# Eddy_Backplane.net
KiCad netlist of a schematic drawn in EAGLE
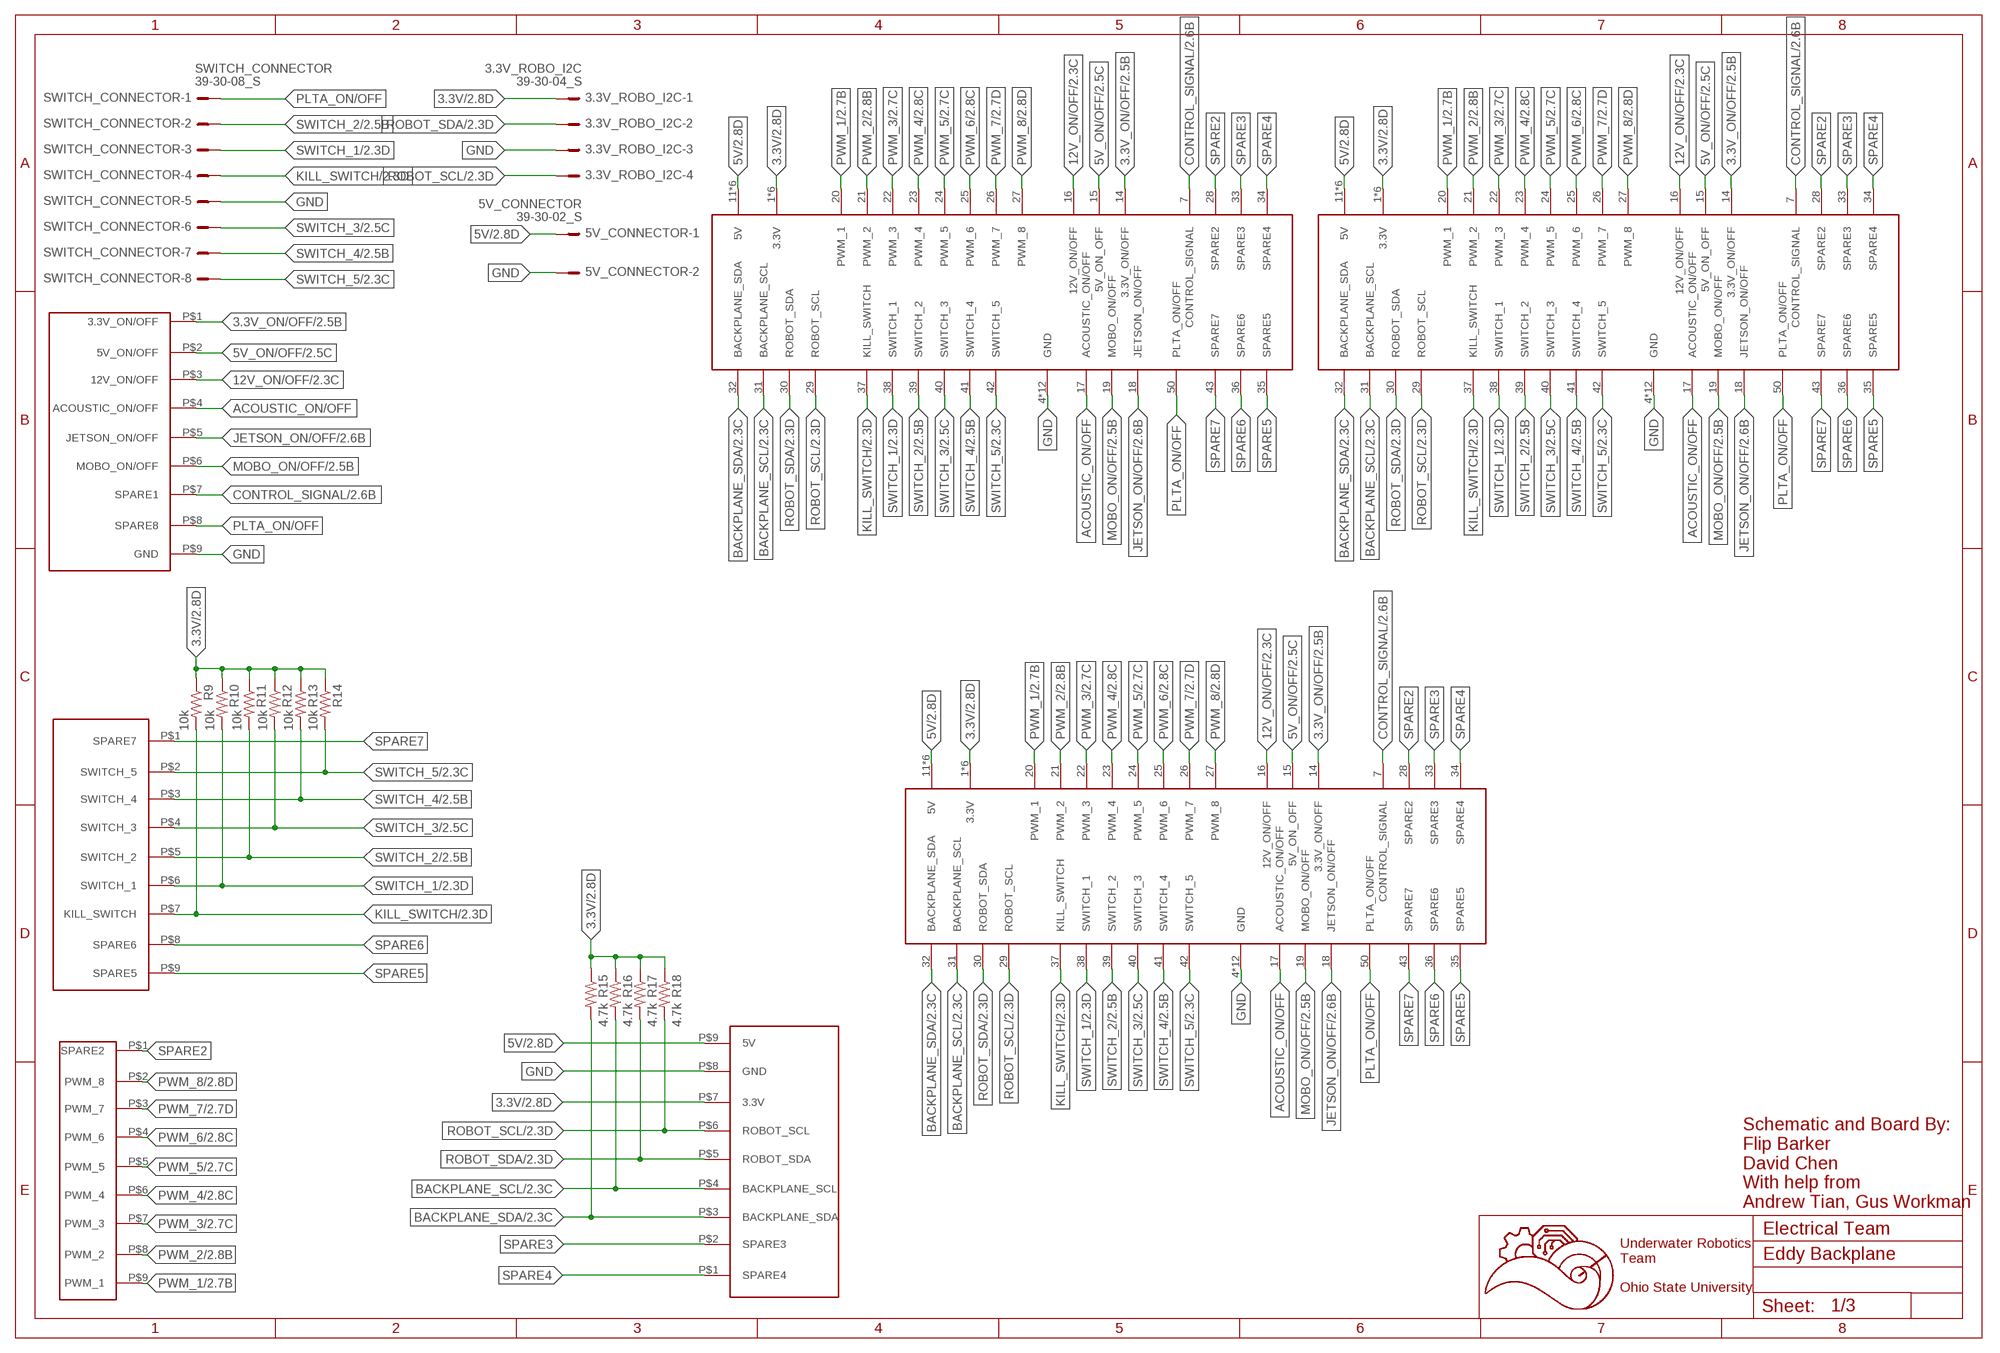
[diagram p0: schematic, sheet 1]
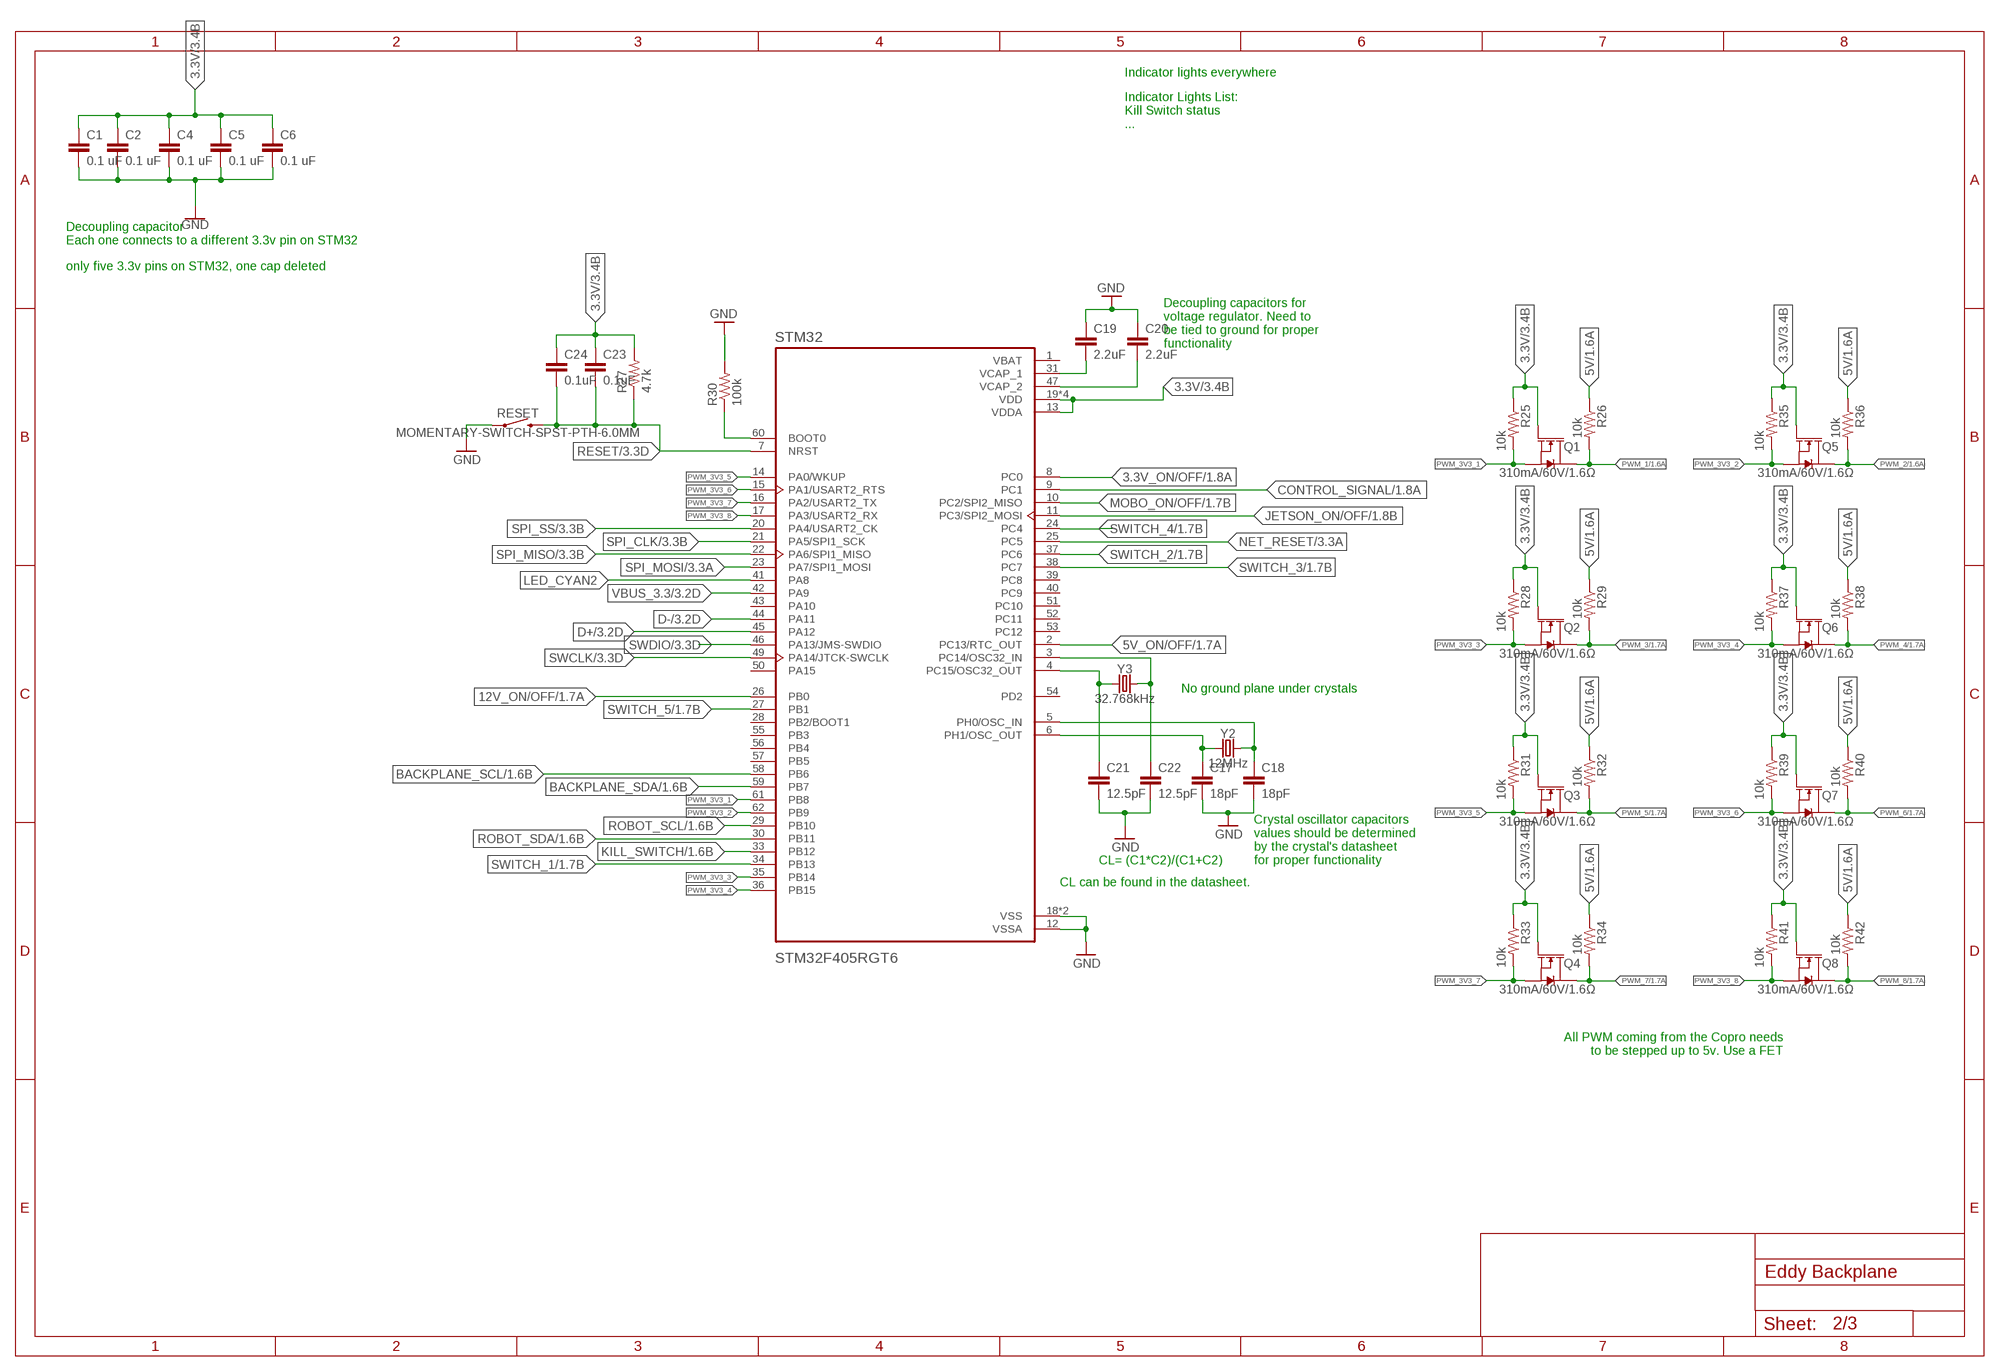
[diagram p1: schematic, sheet 2]
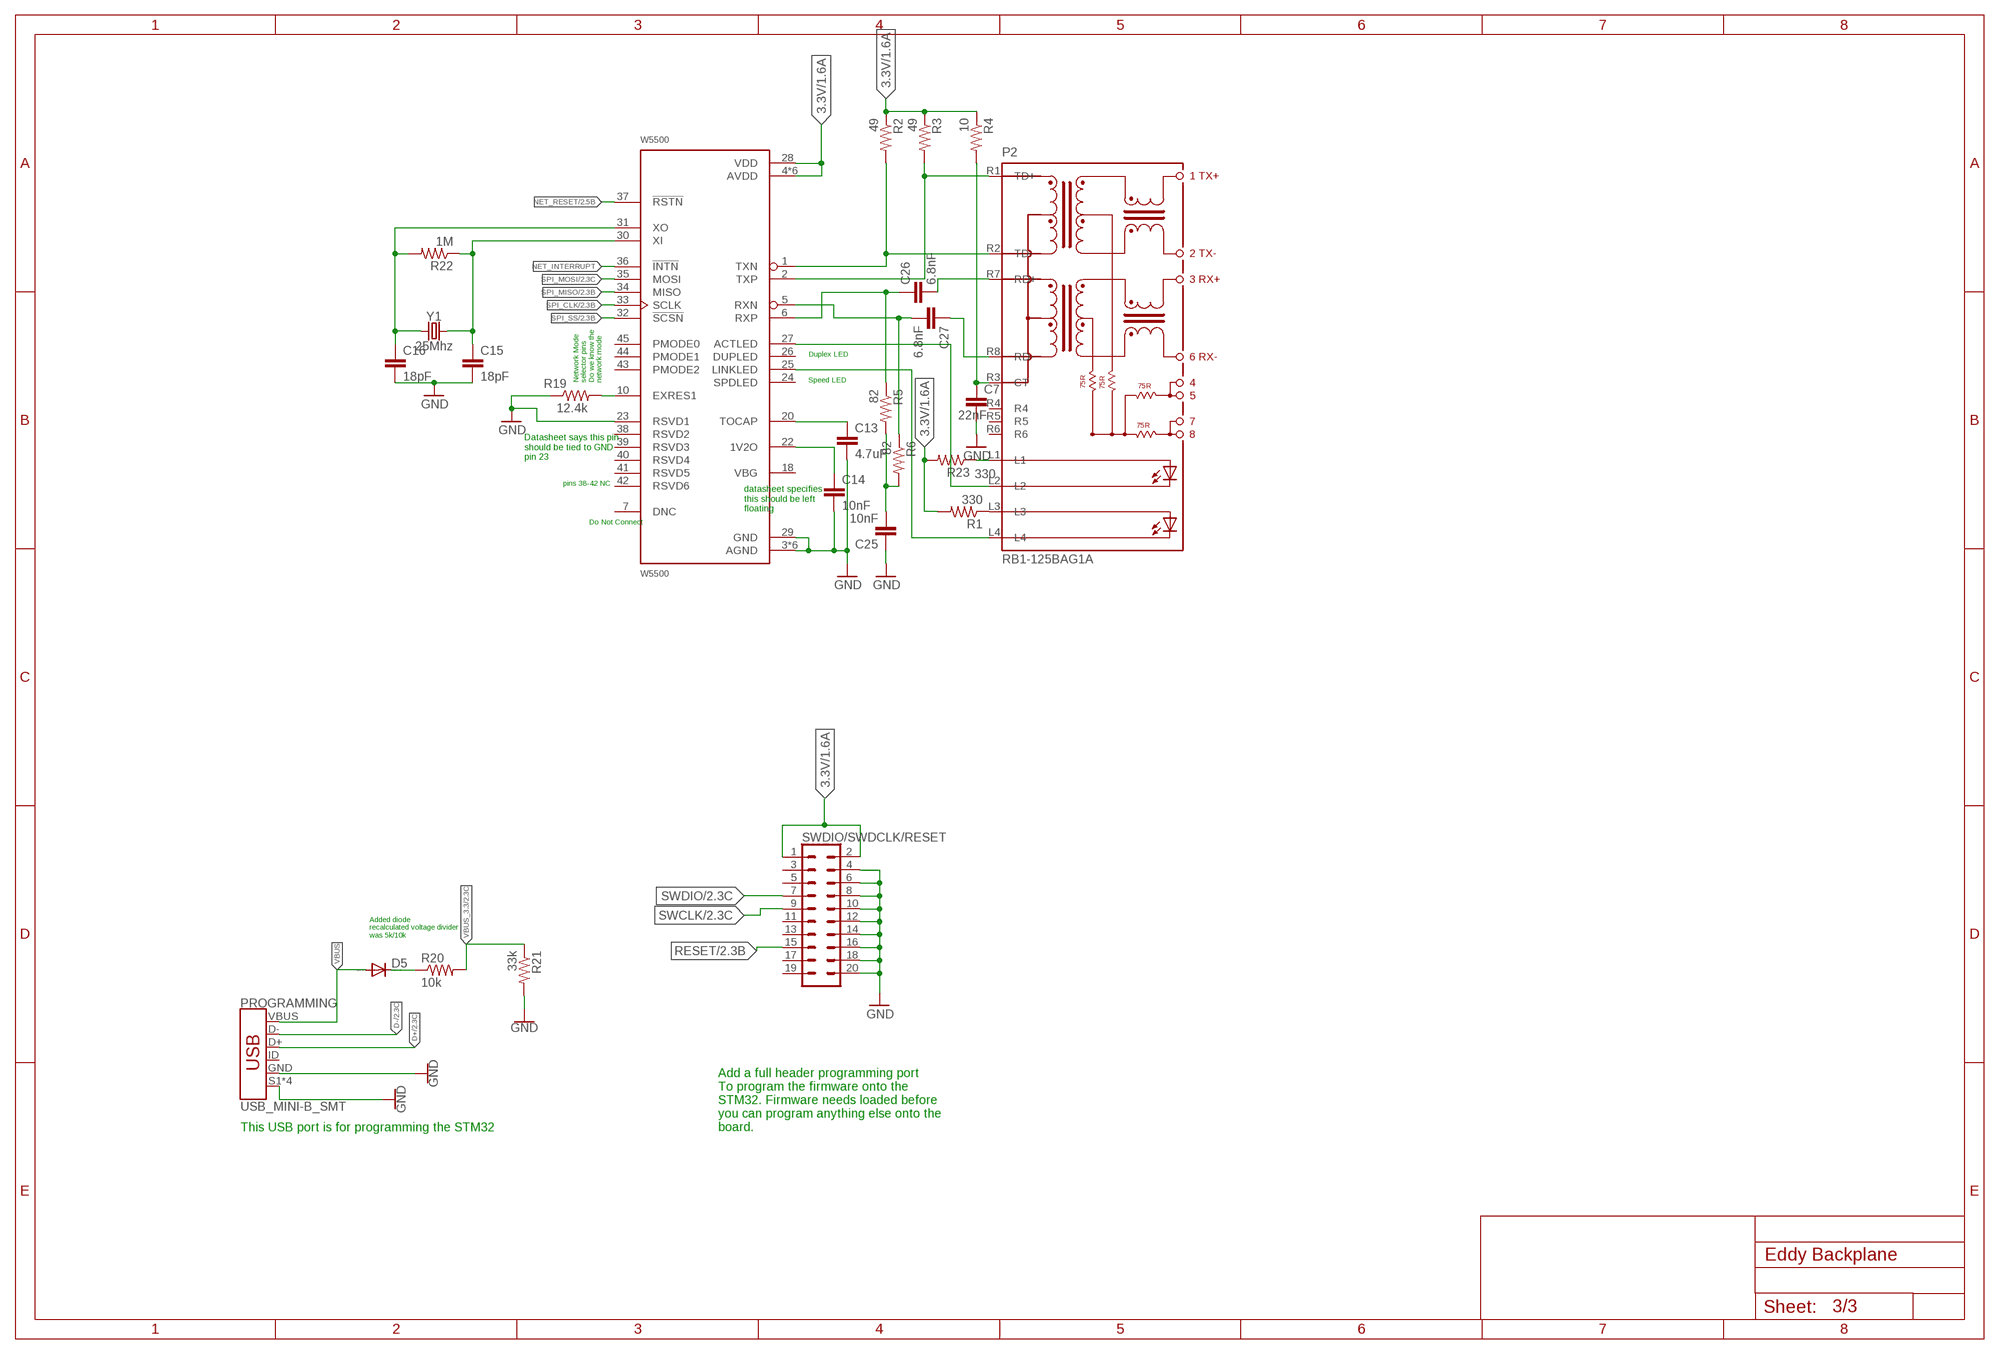
[diagram p2: schematic, sheet 3]

(export (version "E")
  (design (tool "Eeschema 10.0.6"))
  (components
    (comp (ref "C7")
      (value "22nF")
      (footprint "eagle-import:C0603")
      (libsource (lib "eagle-import") (part "C-EUC0603"))
    )
    (comp (ref "C13")
      (value "4.7uF")
      (footprint "eagle-import:C0603")
      (libsource (lib "eagle-import") (part "C-EUC0603"))
    )
    (comp (ref "C14")
      (value "10nF")
      (footprint "eagle-import:C0603")
      (libsource (lib "eagle-import") (part "C-EUC0603"))
    )
    (comp (ref "C15")
      (value "18pF")
      (footprint "eagle-import:C0603")
      (libsource (lib "eagle-import") (part "C-EUC0603"))
    )
    (comp (ref "C16")
      (value "18pF")
      (footprint "eagle-import:C0603")
      (libsource (lib "eagle-import") (part "C-EUC0603"))
    )
    (comp (ref "C25")
      (value "10nF")
      (footprint "eagle-import:C0603")
      (libsource (lib "eagle-import") (part "C-EUC0603"))
    )
    (comp (ref "C26")
      (value "6.8nF")
      (footprint "eagle-import:C0603")
      (libsource (lib "eagle-import") (part "C-EUC0603"))
    )
    (comp (ref "C27")
      (value "6.8nF")
      (footprint "eagle-import:C0603")
      (libsource (lib "eagle-import") (part "C-EUC0603"))
    )
    (comp (ref "D5")
      (value "DIODE-SMB")
      (footprint "eagle-import:SMB")
      (libsource (lib "eagle-import") (part "DIODE-SMB"))
    )
    (comp (ref "P2")
      (value "RB1-125BAG1A")
      (footprint "eagle-import:WIZNET_RB1-125BAG1A")
      (fields (field (name "MF") "WIZnet"))
      (libsource (lib "eagle-import") (part "RB1-125BAG1A"))
    )
    (comp (ref "PROGRAMMING")
      (value "USB_MINI-B_SMT")
      (footprint "eagle-import:USB-MINIB")
      (libsource (lib "eagle-import") (part "USB_MINI-B_SMT"))
    )
    (comp (ref "R1")
      (value "330")
      (footprint "eagle-import:R0603")
      (libsource (lib "eagle-import") (part "R-US_R0603"))
    )
    (comp (ref "R2")
      (value "49")
      (footprint "eagle-import:R0603")
      (libsource (lib "eagle-import") (part "R-US_R0603"))
    )
    (comp (ref "R3")
      (value "49")
      (footprint "eagle-import:R0603")
      (libsource (lib "eagle-import") (part "R-US_R0603"))
    )
    (comp (ref "R4")
      (value "10")
      (footprint "eagle-import:R0603")
      (libsource (lib "eagle-import") (part "R-US_R0603"))
    )
    (comp (ref "R5")
      (value "82")
      (footprint "eagle-import:R0603")
      (libsource (lib "eagle-import") (part "R-US_R0603"))
    )
    (comp (ref "R6")
      (value "82")
      (footprint "eagle-import:R0603")
      (libsource (lib "eagle-import") (part "R-US_R0603"))
    )
    (comp (ref "R19")
      (value "12.4k")
      (footprint "eagle-import:R0603")
      (libsource (lib "eagle-import") (part "R-US_R0603"))
    )
    (comp (ref "R20")
      (value "10k")
      (footprint "eagle-import:R0603")
      (libsource (lib "eagle-import") (part "R-US_R0603"))
    )
    (comp (ref "R21")
      (value "33k")
      (footprint "eagle-import:R0603")
      (libsource (lib "eagle-import") (part "R-US_R0603"))
    )
    (comp (ref "R22")
      (value "1M")
      (footprint "eagle-import:R0603")
      (libsource (lib "eagle-import") (part "R-US_R0603"))
    )
    (comp (ref "R23")
      (value "330")
      (footprint "eagle-import:R0603")
      (libsource (lib "eagle-import") (part "R-US_R0603"))
    )
    (comp (ref "SWDIO/SWDCLK/RESET")
      (value "CONN_10X2")
      (footprint "eagle-import:2X10")
      (libsource (lib "eagle-import") (part "CONN_10X2"))
    )
    (comp (ref "W5500")
      (value "W5500")
      (footprint "eagle-import:QFP50P900X900X160-48N")
      (fields (field (name "MF") "WIZnet"))
      (libsource (lib "eagle-import") (part "W5500"))
    )
    (comp (ref "Y1")
      (value "25Mhz")
      (footprint "eagle-import:HC49US")
      (libsource (lib "eagle-import") (part "CRYSTALPTH-HC49US"))
    )
    (comp (ref "3.3V_ROBO_I2C")
      (value "39-30-04_S")
      (footprint "eagle-import:39-30-_04_")
      (libsource (lib "eagle-import") (part "39-30-?04?_S"))
    )
    (comp (ref "5V_CONNECTOR")
      (value "39-30-02_S")
      (footprint "eagle-import:39-30-_02_")
      (libsource (lib "eagle-import") (part "39-30-?02?_S"))
    )
    (comp (ref "PWR_ON")
      (value "929870-01-09_3")
      (footprint "eagle-import:929852-01-09_1ROW")
      (libsource (lib "eagle-import") (part "929870-01-09_3"))
    )
    (comp (ref "R9")
      (value "10k")
      (footprint "eagle-import:R0603")
      (libsource (lib "eagle-import") (part "R-US_R0603"))
    )
    (comp (ref "R10")
      (value "10k")
      (footprint "eagle-import:R0603")
      (libsource (lib "eagle-import") (part "R-US_R0603"))
    )
    (comp (ref "R11")
      (value "10k")
      (footprint "eagle-import:R0603")
      (libsource (lib "eagle-import") (part "R-US_R0603"))
    )
    (comp (ref "R12")
      (value "10k")
      (footprint "eagle-import:R0603")
      (libsource (lib "eagle-import") (part "R-US_R0603"))
    )
    (comp (ref "R13")
      (value "10k")
      (footprint "eagle-import:R0603")
      (libsource (lib "eagle-import") (part "R-US_R0603"))
    )
    (comp (ref "R14")
      (value "10k")
      (footprint "eagle-import:R0603")
      (libsource (lib "eagle-import") (part "R-US_R0603"))
    )
    (comp (ref "R15")
      (value "4.7k")
      (footprint "eagle-import:R0603")
      (libsource (lib "eagle-import") (part "R-US_R0603"))
    )
    (comp (ref "R16")
      (value "4.7k")
      (footprint "eagle-import:R0603")
      (libsource (lib "eagle-import") (part "R-US_R0603"))
    )
    (comp (ref "R17")
      (value "4.7k")
      (footprint "eagle-import:R0603")
      (libsource (lib "eagle-import") (part "R-US_R0603"))
    )
    (comp (ref "R18")
      (value "4.7k")
      (footprint "eagle-import:R0603")
      (libsource (lib "eagle-import") (part "R-US_R0603"))
    )
    (comp (ref "SWITCH_CONN")
      (value "929870-01-09_1")
      (footprint "eagle-import:929852-01-09_1ROW")
      (libsource (lib "eagle-import") (part "929870-01-09_1"))
    )
    (comp (ref "SWITCH_CONNECTOR")
      (value "39-30-08_S")
      (footprint "eagle-import:39-30-_08_")
      (libsource (lib "eagle-import") (part "39-30-?08?_S"))
    )
    (comp (ref "U$1")
      (value "5530843-FEMALE")
      (footprint "eagle-import:5530843-6-BACKPLANEMATE")
      (libsource (lib "eagle-import") (part "5530843-FEMALE"))
    )
    (comp (ref "U$2")
      (value "5530843-FEMALE")
      (footprint "eagle-import:5530843-6-BACKPLANEMATE")
      (libsource (lib "eagle-import") (part "5530843-FEMALE"))
    )
    (comp (ref "U$3")
      (value "5530843-FEMALE")
      (footprint "eagle-import:5530843-6-BACKPLANEMATE")
      (libsource (lib "eagle-import") (part "5530843-FEMALE"))
    )
    (comp (ref "U$6")
      (value "929870-01-09_2")
      (footprint "eagle-import:929852-01-09_1ROW")
      (libsource (lib "eagle-import") (part "929870-01-09_2"))
    )
    (comp (ref "U$8")
      (value "929870-01-09_4")
      (footprint "eagle-import:929852-01-09_1ROW")
      (libsource (lib "eagle-import") (part "929870-01-09_4"))
    )
    (comp (ref "C1")
      (value "0.1 uF")
      (footprint "eagle-import:C0603")
      (libsource (lib "eagle-import") (part "C-EUC0603"))
    )
    (comp (ref "C2")
      (value "0.1 uF")
      (footprint "eagle-import:C0603")
      (libsource (lib "eagle-import") (part "C-EUC0603"))
    )
    (comp (ref "C4")
      (value "0.1 uF")
      (footprint "eagle-import:C0603")
      (libsource (lib "eagle-import") (part "C-EUC0603"))
    )
    (comp (ref "C5")
      (value "0.1 uF")
      (footprint "eagle-import:C0603")
      (libsource (lib "eagle-import") (part "C-EUC0603"))
    )
    (comp (ref "C6")
      (value "0.1 uF")
      (footprint "eagle-import:C0603")
      (libsource (lib "eagle-import") (part "C-EUC0603"))
    )
    (comp (ref "C17")
      (value "18pF")
      (footprint "eagle-import:C0603")
      (libsource (lib "eagle-import") (part "C-EUC0603"))
    )
    (comp (ref "C18")
      (value "18pF")
      (footprint "eagle-import:C0603")
      (libsource (lib "eagle-import") (part "C-EUC0603"))
    )
    (comp (ref "C19")
      (value "2.2uF")
      (footprint "eagle-import:C0603")
      (libsource (lib "eagle-import") (part "C-EUC0603"))
    )
    (comp (ref "C20")
      (value "2.2uF")
      (footprint "eagle-import:C0603")
      (libsource (lib "eagle-import") (part "C-EUC0603"))
    )
    (comp (ref "C21")
      (value "12.5pF")
      (footprint "eagle-import:C0603")
      (libsource (lib "eagle-import") (part "C-EUC0603"))
    )
    (comp (ref "C22")
      (value "12.5pF")
      (footprint "eagle-import:C0603")
      (libsource (lib "eagle-import") (part "C-EUC0603"))
    )
    (comp (ref "C23")
      (value "0.1uF")
      (footprint "eagle-import:C0603")
      (libsource (lib "eagle-import") (part "C-EUC0603"))
    )
    (comp (ref "C24")
      (value "0.1uF")
      (footprint "eagle-import:C0603")
      (libsource (lib "eagle-import") (part "C-EUC0603"))
    )
    (comp (ref "Q1")
      (value "310mA/60V/1.6Ω")
      (footprint "eagle-import:SOT323")
      (libsource (lib "eagle-import") (part "MOSFET-NCH-2N7002PW"))
    )
    (comp (ref "Q2")
      (value "310mA/60V/1.6Ω")
      (footprint "eagle-import:SOT323")
      (libsource (lib "eagle-import") (part "MOSFET-NCH-2N7002PW"))
    )
    (comp (ref "Q3")
      (value "310mA/60V/1.6Ω")
      (footprint "eagle-import:SOT323")
      (libsource (lib "eagle-import") (part "MOSFET-NCH-2N7002PW"))
    )
    (comp (ref "Q4")
      (value "310mA/60V/1.6Ω")
      (footprint "eagle-import:SOT323")
      (libsource (lib "eagle-import") (part "MOSFET-NCH-2N7002PW"))
    )
    (comp (ref "Q5")
      (value "310mA/60V/1.6Ω")
      (footprint "eagle-import:SOT323")
      (libsource (lib "eagle-import") (part "MOSFET-NCH-2N7002PW"))
    )
    (comp (ref "Q6")
      (value "310mA/60V/1.6Ω")
      (footprint "eagle-import:SOT323")
      (libsource (lib "eagle-import") (part "MOSFET-NCH-2N7002PW"))
    )
    (comp (ref "Q7")
      (value "310mA/60V/1.6Ω")
      (footprint "eagle-import:SOT323")
      (libsource (lib "eagle-import") (part "MOSFET-NCH-2N7002PW"))
    )
    (comp (ref "Q8")
      (value "310mA/60V/1.6Ω")
      (footprint "eagle-import:SOT323")
      (libsource (lib "eagle-import") (part "MOSFET-NCH-2N7002PW"))
    )
    (comp (ref "R25")
      (value "10k")
      (footprint "eagle-import:R0603")
      (libsource (lib "eagle-import") (part "R-US_R0603"))
    )
    (comp (ref "R26")
      (value "10k")
      (footprint "eagle-import:R0603")
      (libsource (lib "eagle-import") (part "R-US_R0603"))
    )
    (comp (ref "R27")
      (value "4.7k")
      (footprint "eagle-import:R0603")
      (libsource (lib "eagle-import") (part "R-US_R0603"))
    )
    (comp (ref "R28")
      (value "10k")
      (footprint "eagle-import:R0603")
      (libsource (lib "eagle-import") (part "R-US_R0603"))
    )
    (comp (ref "R29")
      (value "10k")
      (footprint "eagle-import:R0603")
      (libsource (lib "eagle-import") (part "R-US_R0603"))
    )
    (comp (ref "R30")
      (value "100k")
      (footprint "eagle-import:R0603")
      (libsource (lib "eagle-import") (part "R-US_R0603"))
    )
    (comp (ref "R31")
      (value "10k")
      (footprint "eagle-import:R0603")
      (libsource (lib "eagle-import") (part "R-US_R0603"))
    )
    (comp (ref "R32")
      (value "10k")
      (footprint "eagle-import:R0603")
      (libsource (lib "eagle-import") (part "R-US_R0603"))
    )
    (comp (ref "R33")
      (value "10k")
      (footprint "eagle-import:R0603")
      (libsource (lib "eagle-import") (part "R-US_R0603"))
    )
    (comp (ref "R34")
      (value "10k")
      (footprint "eagle-import:R0603")
      (libsource (lib "eagle-import") (part "R-US_R0603"))
    )
    (comp (ref "R35")
      (value "10k")
      (footprint "eagle-import:R0603")
      (libsource (lib "eagle-import") (part "R-US_R0603"))
    )
    (comp (ref "R36")
      (value "10k")
      (footprint "eagle-import:R0603")
      (libsource (lib "eagle-import") (part "R-US_R0603"))
    )
    (comp (ref "R37")
      (value "10k")
      (footprint "eagle-import:R0603")
      (libsource (lib "eagle-import") (part "R-US_R0603"))
    )
    (comp (ref "R38")
      (value "10k")
      (footprint "eagle-import:R0603")
      (libsource (lib "eagle-import") (part "R-US_R0603"))
    )
    (comp (ref "R39")
      (value "10k")
      (footprint "eagle-import:R0603")
      (libsource (lib "eagle-import") (part "R-US_R0603"))
    )
    (comp (ref "R40")
      (value "10k")
      (footprint "eagle-import:R0603")
      (libsource (lib "eagle-import") (part "R-US_R0603"))
    )
    (comp (ref "R41")
      (value "10k")
      (footprint "eagle-import:R0603")
      (libsource (lib "eagle-import") (part "R-US_R0603"))
    )
    (comp (ref "R42")
      (value "10k")
      (footprint "eagle-import:R0603")
      (libsource (lib "eagle-import") (part "R-US_R0603"))
    )
    (comp (ref "RESET")
      (value "MOMENTARY-SWITCH-SPST-PTH-6.0MM")
      (footprint "eagle-import:TACTILE_SWITCH_PTH_6.0MM")
      (libsource (lib "eagle-import") (part "MOMENTARY-SWITCH-SPST-PTH-6.0MM"))
    )
    (comp (ref "STM32")
      (value "STM32F405RGT6")
      (footprint "eagle-import:QFP50P1200X1200X160-64N")
      (fields (field (name "MF") "STMicroelectronics"))
      (libsource (lib "eagle-import") (part "STM32F405RGT6"))
    )
    (comp (ref "Y2")
      (value "12MHz")
      (footprint "eagle-import:HC49US")
      (libsource (lib "eagle-import") (part "CRYSTAL-16MHZPTH-HC49US"))
    )
    (comp (ref "Y3")
      (value "32.768kHz")
      (footprint "eagle-import:CRYSTAL-SMD-3.2X1.5MM")
      (libsource (lib "eagle-import") (part "CRYSTAL-32.768KHZSMD-3.2X1.5"))
    )
  )
  (nets
    (net (code "1") (name "3.3V") (class "Default")
      (node (ref "3.3V_ROBO_I2C") (pin "1") (pinfunction "P_1") (pintype "passive"))
      (node (ref "C1") (pin "1") (pinfunction "1_1") (pintype "passive"))
      (node (ref "C2") (pin "1") (pinfunction "1_1") (pintype "passive"))
      (node (ref "C23") (pin "1") (pinfunction "1_1") (pintype "passive"))
      (node (ref "C24") (pin "1") (pinfunction "1_1") (pintype "passive"))
      (node (ref "C4") (pin "1") (pinfunction "1_1") (pintype "passive"))
      (node (ref "C5") (pin "1") (pinfunction "1_1") (pintype "passive"))
      (node (ref "C6") (pin "1") (pinfunction "1_1") (pintype "passive"))
      (node (ref "Q1") (pin "1") (pinfunction "G_1") (pintype "bidirectional"))
      (node (ref "Q2") (pin "1") (pinfunction "G_1") (pintype "bidirectional"))
      (node (ref "Q3") (pin "1") (pinfunction "G_1") (pintype "bidirectional"))
      (node (ref "Q4") (pin "1") (pinfunction "G_1") (pintype "bidirectional"))
      (node (ref "Q5") (pin "1") (pinfunction "G_1") (pintype "bidirectional"))
      (node (ref "Q6") (pin "1") (pinfunction "G_1") (pintype "bidirectional"))
      (node (ref "Q7") (pin "1") (pinfunction "G_1") (pintype "bidirectional"))
      (node (ref "Q8") (pin "1") (pinfunction "G_1") (pintype "bidirectional"))
      (node (ref "R1") (pin "2") (pinfunction "2_2") (pintype "passive"))
      (node (ref "R10") (pin "1") (pinfunction "1_1") (pintype "passive"))
      (node (ref "R11") (pin "1") (pinfunction "1_1") (pintype "passive"))
      (node (ref "R12") (pin "1") (pinfunction "1_1") (pintype "passive"))
      (node (ref "R13") (pin "1") (pinfunction "1_1") (pintype "passive"))
      (node (ref "R14") (pin "1") (pinfunction "1_1") (pintype "passive"))
      (node (ref "R15") (pin "1") (pinfunction "1_1") (pintype "passive"))
      (node (ref "R16") (pin "1") (pinfunction "1_1") (pintype "passive"))
      (node (ref "R17") (pin "1") (pinfunction "1_1") (pintype "passive"))
      (node (ref "R18") (pin "1") (pinfunction "1_1") (pintype "passive"))
      (node (ref "R2") (pin "1") (pinfunction "1_1") (pintype "passive"))
      (node (ref "R23") (pin "2") (pinfunction "2_2") (pintype "passive"))
      (node (ref "R25") (pin "1") (pinfunction "1_1") (pintype "passive"))
      (node (ref "R27") (pin "2") (pinfunction "2_2") (pintype "passive"))
      (node (ref "R28") (pin "1") (pinfunction "1_1") (pintype "passive"))
      (node (ref "R3") (pin "1") (pinfunction "1_1") (pintype "passive"))
      (node (ref "R31") (pin "1") (pinfunction "1_1") (pintype "passive"))
      (node (ref "R33") (pin "1") (pinfunction "1_1") (pintype "passive"))
      (node (ref "R35") (pin "1") (pinfunction "1_1") (pintype "passive"))
      (node (ref "R37") (pin "1") (pinfunction "1_1") (pintype "passive"))
      (node (ref "R39") (pin "1") (pinfunction "1_1") (pintype "passive"))
      (node (ref "R4") (pin "1") (pinfunction "1_1") (pintype "passive"))
      (node (ref "R41") (pin "1") (pinfunction "1_1") (pintype "passive"))
      (node (ref "R9") (pin "1") (pinfunction "1_1") (pintype "passive"))
      (node (ref "STM32") (pin "13") (pinfunction "VDDA_13") (pintype "power_in"))
      (node (ref "STM32") (pin "19") (pinfunction "VDD_19") (pintype "power_in"))
      (node (ref "STM32") (pin "32") (pinfunction "VDD_32") (pintype "power_in"))
      (node (ref "STM32") (pin "48") (pinfunction "VDD_48") (pintype "power_in"))
      (node (ref "STM32") (pin "64") (pinfunction "VDD_64") (pintype "power_in"))
      (node (ref "SWDIO/SWDCLK/RESET") (pin "1") (pinfunction "1_1") (pintype "passive"))
      (node (ref "SWDIO/SWDCLK/RESET") (pin "2") (pinfunction "2_2") (pintype "passive"))
      (node (ref "U$1") (pin "1") (pinfunction "3.3V_1") (pintype "bidirectional"))
      (node (ref "U$1") (pin "2") (pinfunction "3.3V_2") (pintype "bidirectional"))
      (node (ref "U$1") (pin "3") (pinfunction "3.3V_3") (pintype "bidirectional"))
      (node (ref "U$1") (pin "54") (pinfunction "3.3V_54") (pintype "bidirectional"))
      (node (ref "U$1") (pin "55") (pinfunction "3.3V_55") (pintype "bidirectional"))
      (node (ref "U$1") (pin "56") (pinfunction "3.3V_56") (pintype "bidirectional"))
      (node (ref "U$2") (pin "1") (pinfunction "3.3V_1") (pintype "bidirectional"))
      (node (ref "U$2") (pin "2") (pinfunction "3.3V_2") (pintype "bidirectional"))
      (node (ref "U$2") (pin "3") (pinfunction "3.3V_3") (pintype "bidirectional"))
      (node (ref "U$2") (pin "54") (pinfunction "3.3V_54") (pintype "bidirectional"))
      (node (ref "U$2") (pin "55") (pinfunction "3.3V_55") (pintype "bidirectional"))
      (node (ref "U$2") (pin "56") (pinfunction "3.3V_56") (pintype "bidirectional"))
      (node (ref "U$3") (pin "1") (pinfunction "3.3V_1") (pintype "bidirectional"))
      (node (ref "U$3") (pin "2") (pinfunction "3.3V_2") (pintype "bidirectional"))
      (node (ref "U$3") (pin "3") (pinfunction "3.3V_3") (pintype "bidirectional"))
      (node (ref "U$3") (pin "54") (pinfunction "3.3V_54") (pintype "bidirectional"))
      (node (ref "U$3") (pin "55") (pinfunction "3.3V_55") (pintype "bidirectional"))
      (node (ref "U$3") (pin "56") (pinfunction "3.3V_56") (pintype "bidirectional"))
      (node (ref "U$8") (pin "P$7") (pinfunction "3.3V_P$7") (pintype "bidirectional"))
      (node (ref "W5500") (pin "11") (pinfunction "AVDD_11") (pintype "power_in"))
      (node (ref "W5500") (pin "15") (pinfunction "AVDD_15") (pintype "power_in"))
      (node (ref "W5500") (pin "17") (pinfunction "AVDD_17") (pintype "power_in"))
      (node (ref "W5500") (pin "21") (pinfunction "AVDD_21") (pintype "power_in"))
      (node (ref "W5500") (pin "28") (pinfunction "VDD_28") (pintype "power_in"))
      (node (ref "W5500") (pin "4") (pinfunction "AVDD_4") (pintype "power_in"))
      (node (ref "W5500") (pin "8") (pinfunction "AVDD_8") (pintype "power_in"))
    )
    (net (code "2") (name "3.3V_ON{slash}OFF") (class "Default")
      (node (ref "PWR_ON") (pin "P$1") (pinfunction "3.3V_ON/OFF_P$1") (pintype "bidirectional"))
      (node (ref "STM32") (pin "8") (pinfunction "PC0_8") (pintype "bidirectional"))
      (node (ref "U$1") (pin "14") (pinfunction "3.3V_ON/OFF_14") (pintype "bidirectional"))
      (node (ref "U$2") (pin "14") (pinfunction "3.3V_ON/OFF_14") (pintype "bidirectional"))
      (node (ref "U$3") (pin "14") (pinfunction "3.3V_ON/OFF_14") (pintype "bidirectional"))
    )
    (net (code "3") (name "5V") (class "Default")
      (node (ref "5V_CONNECTOR") (pin "1") (pinfunction "P_1") (pintype "passive"))
      (node (ref "R26") (pin "1") (pinfunction "1_1") (pintype "passive"))
      (node (ref "R29") (pin "1") (pinfunction "1_1") (pintype "passive"))
      (node (ref "R32") (pin "1") (pinfunction "1_1") (pintype "passive"))
      (node (ref "R34") (pin "1") (pinfunction "1_1") (pintype "passive"))
      (node (ref "R36") (pin "1") (pinfunction "1_1") (pintype "passive"))
      (node (ref "R38") (pin "1") (pinfunction "1_1") (pintype "passive"))
      (node (ref "R40") (pin "1") (pinfunction "1_1") (pintype "passive"))
      (node (ref "R42") (pin "1") (pinfunction "1_1") (pintype "passive"))
      (node (ref "U$1") (pin "11") (pinfunction "5V_11") (pintype "bidirectional"))
      (node (ref "U$1") (pin "12") (pinfunction "5V_12") (pintype "bidirectional"))
      (node (ref "U$1") (pin "13") (pinfunction "5V_13") (pintype "bidirectional"))
      (node (ref "U$1") (pin "44") (pinfunction "5V_44") (pintype "bidirectional"))
      (node (ref "U$1") (pin "45") (pinfunction "5V_45") (pintype "bidirectional"))
      (node (ref "U$1") (pin "46") (pinfunction "5V_46") (pintype "bidirectional"))
      (node (ref "U$2") (pin "11") (pinfunction "5V_11") (pintype "bidirectional"))
      (node (ref "U$2") (pin "12") (pinfunction "5V_12") (pintype "bidirectional"))
      (node (ref "U$2") (pin "13") (pinfunction "5V_13") (pintype "bidirectional"))
      (node (ref "U$2") (pin "44") (pinfunction "5V_44") (pintype "bidirectional"))
      (node (ref "U$2") (pin "45") (pinfunction "5V_45") (pintype "bidirectional"))
      (node (ref "U$2") (pin "46") (pinfunction "5V_46") (pintype "bidirectional"))
      (node (ref "U$3") (pin "11") (pinfunction "5V_11") (pintype "bidirectional"))
      (node (ref "U$3") (pin "12") (pinfunction "5V_12") (pintype "bidirectional"))
      (node (ref "U$3") (pin "13") (pinfunction "5V_13") (pintype "bidirectional"))
      (node (ref "U$3") (pin "44") (pinfunction "5V_44") (pintype "bidirectional"))
      (node (ref "U$3") (pin "45") (pinfunction "5V_45") (pintype "bidirectional"))
      (node (ref "U$3") (pin "46") (pinfunction "5V_46") (pintype "bidirectional"))
      (node (ref "U$8") (pin "P$9") (pinfunction "5V_P$9") (pintype "bidirectional"))
    )
    (net (code "4") (name "5V_ON{slash}OFF") (class "Default")
      (node (ref "PWR_ON") (pin "P$2") (pinfunction "5V_ON/OFF_P$2") (pintype "bidirectional"))
      (node (ref "STM32") (pin "2") (pinfunction "PC13/RTC_OUT_2") (pintype "bidirectional"))
      (node (ref "U$1") (pin "15") (pinfunction "5V_ON_OFF_15") (pintype "bidirectional"))
      (node (ref "U$2") (pin "15") (pinfunction "5V_ON_OFF_15") (pintype "bidirectional"))
      (node (ref "U$3") (pin "15") (pinfunction "5V_ON_OFF_15") (pintype "bidirectional"))
    )
    (net (code "5") (name "12V_ON{slash}OFF") (class "Default")
      (node (ref "PWR_ON") (pin "P$3") (pinfunction "12V_ON/OFF_P$3") (pintype "bidirectional"))
      (node (ref "STM32") (pin "26") (pinfunction "PB0_26") (pintype "bidirectional"))
      (node (ref "U$1") (pin "16") (pinfunction "12V_ON/OFF_16") (pintype "bidirectional"))
      (node (ref "U$2") (pin "16") (pinfunction "12V_ON/OFF_16") (pintype "bidirectional"))
      (node (ref "U$3") (pin "16") (pinfunction "12V_ON/OFF_16") (pintype "bidirectional"))
    )
    (net (code "6") (name "ACOUSTIC_ON{slash}OFF") (class "Default")
      (node (ref "PWR_ON") (pin "P$4") (pinfunction "ACOUSTIC_ON/OFF_P$4") (pintype "bidirectional"))
      (node (ref "U$1") (pin "17") (pinfunction "ACOUSTIC_ON/OFF_17") (pintype "bidirectional"))
      (node (ref "U$2") (pin "17") (pinfunction "ACOUSTIC_ON/OFF_17") (pintype "bidirectional"))
      (node (ref "U$3") (pin "17") (pinfunction "ACOUSTIC_ON/OFF_17") (pintype "bidirectional"))
    )
    (net (code "7") (name "BACKPLANE_SCL") (class "Default")
      (node (ref "R16") (pin "2") (pinfunction "2_2") (pintype "passive"))
      (node (ref "STM32") (pin "58") (pinfunction "PB6_58") (pintype "bidirectional"))
      (node (ref "U$1") (pin "31") (pinfunction "BACKPLANE_SCL_31") (pintype "bidirectional"))
      (node (ref "U$2") (pin "31") (pinfunction "BACKPLANE_SCL_31") (pintype "bidirectional"))
      (node (ref "U$3") (pin "31") (pinfunction "BACKPLANE_SCL_31") (pintype "bidirectional"))
      (node (ref "U$8") (pin "P$4") (pinfunction "BACKPLANE_SCL_P$4") (pintype "bidirectional"))
    )
    (net (code "8") (name "BACKPLANE_SDA") (class "Default")
      (node (ref "R15") (pin "2") (pinfunction "2_2") (pintype "passive"))
      (node (ref "STM32") (pin "59") (pinfunction "PB7_59") (pintype "bidirectional"))
      (node (ref "U$1") (pin "32") (pinfunction "BACKPLANE_SDA_32") (pintype "bidirectional"))
      (node (ref "U$2") (pin "32") (pinfunction "BACKPLANE_SDA_32") (pintype "bidirectional"))
      (node (ref "U$3") (pin "32") (pinfunction "BACKPLANE_SDA_32") (pintype "bidirectional"))
      (node (ref "U$8") (pin "P$3") (pinfunction "BACKPLANE_SDA_P$3") (pintype "bidirectional"))
    )
    (net (code "9") (name "CONTROL_SIGNAL") (class "Default")
      (node (ref "PWR_ON") (pin "P$7") (pinfunction "SPARE1_P$7") (pintype "bidirectional"))
      (node (ref "STM32") (pin "9") (pinfunction "PC1_9") (pintype "bidirectional"))
      (node (ref "U$1") (pin "7") (pinfunction "CONTROL_SIGNAL_7") (pintype "bidirectional"))
      (node (ref "U$2") (pin "7") (pinfunction "CONTROL_SIGNAL_7") (pintype "bidirectional"))
      (node (ref "U$3") (pin "7") (pinfunction "CONTROL_SIGNAL_7") (pintype "bidirectional"))
    )
    (net (code "10") (name "D+") (class "Default")
      (node (ref "PROGRAMMING") (pin "D+") (pinfunction "D+_D+") (pintype "bidirectional"))
      (node (ref "STM32") (pin "45") (pinfunction "PA12_45") (pintype "bidirectional"))
    )
    (net (code "11") (name "D-") (class "Default")
      (node (ref "PROGRAMMING") (pin "D-") (pinfunction "D-_D-") (pintype "bidirectional"))
      (node (ref "STM32") (pin "44") (pinfunction "PA11_44") (pintype "bidirectional"))
    )
    (net (code "12") (name "GND") (class "Default")
      (node (ref "3.3V_ROBO_I2C") (pin "3") (pinfunction "P_3") (pintype "passive"))
      (node (ref "5V_CONNECTOR") (pin "2") (pinfunction "P_2") (pintype "passive"))
      (node (ref "C1") (pin "2") (pinfunction "2_2") (pintype "passive"))
      (node (ref "C13") (pin "2") (pinfunction "2_2") (pintype "passive"))
      (node (ref "C14") (pin "2") (pinfunction "2_2") (pintype "passive"))
      (node (ref "C15") (pin "2") (pinfunction "2_2") (pintype "passive"))
      (node (ref "C16") (pin "2") (pinfunction "2_2") (pintype "passive"))
      (node (ref "C17") (pin "2") (pinfunction "2_2") (pintype "passive"))
      (node (ref "C18") (pin "2") (pinfunction "2_2") (pintype "passive"))
      (node (ref "C19") (pin "1") (pinfunction "1_1") (pintype "passive"))
      (node (ref "C2") (pin "2") (pinfunction "2_2") (pintype "passive"))
      (node (ref "C20") (pin "1") (pinfunction "1_1") (pintype "passive"))
      (node (ref "C21") (pin "2") (pinfunction "2_2") (pintype "passive"))
      (node (ref "C22") (pin "2") (pinfunction "2_2") (pintype "passive"))
      (node (ref "C25") (pin "1") (pinfunction "1_1") (pintype "passive"))
      (node (ref "C4") (pin "2") (pinfunction "2_2") (pintype "passive"))
      (node (ref "C5") (pin "2") (pinfunction "2_2") (pintype "passive"))
      (node (ref "C6") (pin "2") (pinfunction "2_2") (pintype "passive"))
      (node (ref "C7") (pin "2") (pinfunction "2_2") (pintype "passive"))
      (node (ref "PROGRAMMING") (pin "GND") (pinfunction "GND_GND") (pintype "power_in"))
      (node (ref "PROGRAMMING") (pin "S1") (pinfunction "SHIELD_S1") (pintype "bidirectional"))
      (node (ref "PROGRAMMING") (pin "S2") (pinfunction "SHIELD_S2") (pintype "bidirectional"))
      (node (ref "PROGRAMMING") (pin "S3") (pinfunction "SHIELD_S3") (pintype "bidirectional"))
      (node (ref "PROGRAMMING") (pin "S4") (pinfunction "SHIELD_S4") (pintype "bidirectional"))
      (node (ref "PWR_ON") (pin "P$9") (pinfunction "GND_P$9") (pintype "bidirectional"))
      (node (ref "R19") (pin "1") (pinfunction "1_1") (pintype "passive"))
      (node (ref "R21") (pin "2") (pinfunction "2_2") (pintype "passive"))
      (node (ref "R30") (pin "2") (pinfunction "2_2") (pintype "passive"))
      (node (ref "RESET") (pin "1") (pinfunction "1_1") (pintype "passive"))
      (node (ref "STM32") (pin "12") (pinfunction "VSSA_12") (pintype "power_in"))
      (node (ref "STM32") (pin "18") (pinfunction "VSS_18") (pintype "power_in"))
      (node (ref "STM32") (pin "63") (pinfunction "VSS_63") (pintype "power_in"))
      (node (ref "SWDIO/SWDCLK/RESET") (pin "10") (pinfunction "10_10") (pintype "passive"))
      (node (ref "SWDIO/SWDCLK/RESET") (pin "12") (pinfunction "12_12") (pintype "passive"))
      (node (ref "SWDIO/SWDCLK/RESET") (pin "14") (pinfunction "14_14") (pintype "passive"))
      (node (ref "SWDIO/SWDCLK/RESET") (pin "16") (pinfunction "16_16") (pintype "passive"))
      (node (ref "SWDIO/SWDCLK/RESET") (pin "18") (pinfunction "18_18") (pintype "passive"))
      (node (ref "SWDIO/SWDCLK/RESET") (pin "20") (pinfunction "20_20") (pintype "passive"))
      (node (ref "SWDIO/SWDCLK/RESET") (pin "4") (pinfunction "4_4") (pintype "passive"))
      (node (ref "SWDIO/SWDCLK/RESET") (pin "6") (pinfunction "6_6") (pintype "passive"))
      (node (ref "SWDIO/SWDCLK/RESET") (pin "8") (pinfunction "8_8") (pintype "passive"))
      (node (ref "SWITCH_CONNECTOR") (pin "5") (pinfunction "P_5") (pintype "passive"))
      (node (ref "U$1") (pin "10") (pinfunction "GND_10") (pintype "bidirectional"))
      (node (ref "U$1") (pin "4") (pinfunction "GND_4") (pintype "bidirectional"))
      (node (ref "U$1") (pin "47") (pinfunction "GND_47") (pintype "bidirectional"))
      (node (ref "U$1") (pin "48") (pinfunction "GND_48") (pintype "bidirectional"))
      (node (ref "U$1") (pin "49") (pinfunction "GND_49") (pintype "bidirectional"))
      (node (ref "U$1") (pin "5") (pinfunction "GND_5") (pintype "bidirectional"))
      (node (ref "U$1") (pin "51") (pinfunction "GND_51") (pintype "bidirectional"))
      (node (ref "U$1") (pin "52") (pinfunction "GND_52") (pintype "bidirectional"))
      (node (ref "U$1") (pin "53") (pinfunction "GND_53") (pintype "bidirectional"))
      (node (ref "U$1") (pin "6") (pinfunction "GND_6") (pintype "bidirectional"))
      (node (ref "U$1") (pin "8") (pinfunction "GND_8") (pintype "bidirectional"))
      (node (ref "U$1") (pin "9") (pinfunction "GND_9") (pintype "bidirectional"))
      (node (ref "U$2") (pin "10") (pinfunction "GND_10") (pintype "bidirectional"))
      (node (ref "U$2") (pin "4") (pinfunction "GND_4") (pintype "bidirectional"))
      (node (ref "U$2") (pin "47") (pinfunction "GND_47") (pintype "bidirectional"))
      (node (ref "U$2") (pin "48") (pinfunction "GND_48") (pintype "bidirectional"))
      (node (ref "U$2") (pin "49") (pinfunction "GND_49") (pintype "bidirectional"))
      (node (ref "U$2") (pin "5") (pinfunction "GND_5") (pintype "bidirectional"))
      (node (ref "U$2") (pin "51") (pinfunction "GND_51") (pintype "bidirectional"))
      (node (ref "U$2") (pin "52") (pinfunction "GND_52") (pintype "bidirectional"))
      (node (ref "U$2") (pin "53") (pinfunction "GND_53") (pintype "bidirectional"))
      (node (ref "U$2") (pin "6") (pinfunction "GND_6") (pintype "bidirectional"))
      (node (ref "U$2") (pin "8") (pinfunction "GND_8") (pintype "bidirectional"))
      (node (ref "U$2") (pin "9") (pinfunction "GND_9") (pintype "bidirectional"))
      (node (ref "U$3") (pin "10") (pinfunction "GND_10") (pintype "bidirectional"))
      (node (ref "U$3") (pin "4") (pinfunction "GND_4") (pintype "bidirectional"))
      (node (ref "U$3") (pin "47") (pinfunction "GND_47") (pintype "bidirectional"))
      (node (ref "U$3") (pin "48") (pinfunction "GND_48") (pintype "bidirectional"))
      (node (ref "U$3") (pin "49") (pinfunction "GND_49") (pintype "bidirectional"))
      (node (ref "U$3") (pin "5") (pinfunction "GND_5") (pintype "bidirectional"))
      (node (ref "U$3") (pin "51") (pinfunction "GND_51") (pintype "bidirectional"))
      (node (ref "U$3") (pin "52") (pinfunction "GND_52") (pintype "bidirectional"))
      (node (ref "U$3") (pin "53") (pinfunction "GND_53") (pintype "bidirectional"))
      (node (ref "U$3") (pin "6") (pinfunction "GND_6") (pintype "bidirectional"))
      (node (ref "U$3") (pin "8") (pinfunction "GND_8") (pintype "bidirectional"))
      (node (ref "U$3") (pin "9") (pinfunction "GND_9") (pintype "bidirectional"))
      (node (ref "U$8") (pin "P$8") (pinfunction "GND_P$8") (pintype "bidirectional"))
      (node (ref "W5500") (pin "14") (pinfunction "AGND_14") (pintype "power_in"))
      (node (ref "W5500") (pin "16") (pinfunction "AGND_16") (pintype "power_in"))
      (node (ref "W5500") (pin "19") (pinfunction "AGND_19") (pintype "power_in"))
      (node (ref "W5500") (pin "23") (pinfunction "RSVD1_23") (pintype "input"))
      (node (ref "W5500") (pin "29") (pinfunction "GND_29") (pintype "passive"))
      (node (ref "W5500") (pin "3") (pinfunction "AGND_3") (pintype "power_in"))
      (node (ref "W5500") (pin "48") (pinfunction "AGND_48") (pintype "power_in"))
      (node (ref "W5500") (pin "9") (pinfunction "AGND_9") (pintype "power_in"))
    )
    (net (code "13") (name "JETSON_ON{slash}OFF") (class "Default")
      (node (ref "PWR_ON") (pin "P$5") (pinfunction "JETSON_ON/OFF_P$5") (pintype "bidirectional"))
      (node (ref "STM32") (pin "11") (pinfunction "PC3/SPI2_MOSI_11") (pintype "bidirectional"))
      (node (ref "U$1") (pin "18") (pinfunction "JETSON_ON/OFF_18") (pintype "bidirectional"))
      (node (ref "U$2") (pin "18") (pinfunction "JETSON_ON/OFF_18") (pintype "bidirectional"))
      (node (ref "U$3") (pin "18") (pinfunction "JETSON_ON/OFF_18") (pintype "bidirectional"))
    )
    (net (code "14") (name "KILL_SWITCH") (class "Default")
      (node (ref "R9") (pin "2") (pinfunction "2_2") (pintype "passive"))
      (node (ref "STM32") (pin "33") (pinfunction "PB12_33") (pintype "bidirectional"))
      (node (ref "SWITCH_CONN") (pin "P$7") (pinfunction "KILL_SWITCH_P$7") (pintype "bidirectional"))
      (node (ref "SWITCH_CONNECTOR") (pin "4") (pinfunction "P_4") (pintype "passive"))
      (node (ref "U$1") (pin "37") (pinfunction "KILL_SWITCH_37") (pintype "output"))
      (node (ref "U$2") (pin "37") (pinfunction "KILL_SWITCH_37") (pintype "output"))
      (node (ref "U$3") (pin "37") (pinfunction "KILL_SWITCH_37") (pintype "output"))
    )
    (net (code "15") (name "LED_CYAN2") (class "Default")
      (node (ref "STM32") (pin "41") (pinfunction "PA8_41") (pintype "bidirectional"))
    )
    (net (code "16") (name "MOBO_ON{slash}OFF") (class "Default")
      (node (ref "PWR_ON") (pin "P$6") (pinfunction "MOBO_ON/OFF_P$6") (pintype "bidirectional"))
      (node (ref "STM32") (pin "10") (pinfunction "PC2/SPI2_MISO_10") (pintype "bidirectional"))
      (node (ref "U$1") (pin "19") (pinfunction "MOBO_ON/OFF_19") (pintype "bidirectional"))
      (node (ref "U$2") (pin "19") (pinfunction "MOBO_ON/OFF_19") (pintype "bidirectional"))
      (node (ref "U$3") (pin "19") (pinfunction "MOBO_ON/OFF_19") (pintype "bidirectional"))
    )
    (net (code "17") (name "NET_INTERRUPT") (class "Default")
      (node (ref "W5500") (pin "36") (pinfunction "~{INTN}_36") (pintype "input"))
    )
    (net (code "18") (name "NET_RESET") (class "Default")
      (node (ref "STM32") (pin "25") (pinfunction "PC5_25") (pintype "bidirectional"))
      (node (ref "W5500") (pin "37") (pinfunction "~{RSTN}_37") (pintype "input"))
    )
    (net (code "19") (name "Net-(C25-Pad2)") (class "Default")
      (node (ref "C25") (pin "2") (pinfunction "2_2") (pintype "passive"))
      (node (ref "R5") (pin "2") (pinfunction "2_2") (pintype "passive"))
      (node (ref "R6") (pin "2") (pinfunction "2_2") (pintype "passive"))
    )
    (net (code "20") (name "Net-(D5-PadC)") (class "Default")
      (node (ref "D5") (pin "C") (pinfunction "C_C") (pintype "passive"))
      (node (ref "R20") (pin "1") (pinfunction "1_1") (pintype "passive"))
    )
    (net (code "21") (name "Net-(P2-CT)") (class "Default")
      (node (ref "C7") (pin "1") (pinfunction "1_1") (pintype "passive"))
      (node (ref "P2") (pin "R3") (pinfunction "CT_R3") (pintype "input"))
      (node (ref "R4") (pin "2") (pinfunction "2_2") (pintype "passive"))
    )
    (net (code "22") (name "Net-(P2-PadL1)") (class "Default")
      (node (ref "P2") (pin "L1") (pinfunction "L1_L1") (pintype "passive"))
      (node (ref "R23") (pin "1") (pinfunction "1_1") (pintype "passive"))
    )
    (net (code "23") (name "Net-(P2-PadL3)") (class "Default")
      (node (ref "P2") (pin "L3") (pinfunction "L3_L3") (pintype "passive"))
      (node (ref "R1") (pin "1") (pinfunction "1_1") (pintype "passive"))
    )
    (net (code "24") (name "Net-(P2-RD+)") (class "Default")
      (node (ref "C26") (pin "2") (pinfunction "2_2") (pintype "passive"))
      (node (ref "P2") (pin "R7") (pinfunction "RD+_R7") (pintype "input"))
    )
    (net (code "25") (name "Net-(P2-RD-)") (class "Default")
      (node (ref "C27") (pin "1") (pinfunction "1_1") (pintype "passive"))
      (node (ref "P2") (pin "R8") (pinfunction "RD-_R8") (pintype "input"))
    )
    (net (code "26") (name "Net-(P2-TD+)") (class "Default")
      (node (ref "P2") (pin "R1") (pinfunction "TD+_R1") (pintype "input"))
      (node (ref "R3") (pin "2") (pinfunction "2_2") (pintype "passive"))
      (node (ref "W5500") (pin "2") (pinfunction "TXP_2") (pintype "output"))
    )
    (net (code "27") (name "Net-(P2-TD-)") (class "Default")
      (node (ref "P2") (pin "R2") (pinfunction "TD-_R2") (pintype "input"))
      (node (ref "R2") (pin "2") (pinfunction "2_2") (pintype "passive"))
      (node (ref "W5500") (pin "1") (pinfunction "TXN_1") (pintype "output"))
    )
    (net (code "28") (name "Net-(STM32-BOOT0)") (class "Default")
      (node (ref "R30") (pin "1") (pinfunction "1_1") (pintype "passive"))
      (node (ref "STM32") (pin "60") (pinfunction "BOOT0_60") (pintype "bidirectional"))
    )
    (net (code "29") (name "Net-(STM32-PC14{slash}OSC32_IN)") (class "Default")
      (node (ref "C22") (pin "1") (pinfunction "1_1") (pintype "passive"))
      (node (ref "STM32") (pin "3") (pinfunction "PC14/OSC32_IN_3") (pintype "bidirectional"))
      (node (ref "Y3") (pin "P$2") (pinfunction "2_P$2") (pintype "passive"))
    )
    (net (code "30") (name "Net-(STM32-PC15{slash}OSC32_OUT)") (class "Default")
      (node (ref "C21") (pin "1") (pinfunction "1_1") (pintype "passive"))
      (node (ref "STM32") (pin "4") (pinfunction "PC15/OSC32_OUT_4") (pintype "bidirectional"))
      (node (ref "Y3") (pin "P$1") (pinfunction "1_P$1") (pintype "passive"))
    )
    (net (code "31") (name "Net-(STM32-PH0{slash}OSC_IN)") (class "Default")
      (node (ref "C18") (pin "1") (pinfunction "1_1") (pintype "passive"))
      (node (ref "STM32") (pin "5") (pinfunction "PH0/OSC_IN_5") (pintype "bidirectional"))
      (node (ref "Y2") (pin "2") (pinfunction "2_2") (pintype "passive"))
    )
    (net (code "32") (name "Net-(STM32-PH1{slash}OSC_OUT)") (class "Default")
      (node (ref "C17") (pin "1") (pinfunction "1_1") (pintype "passive"))
      (node (ref "STM32") (pin "6") (pinfunction "PH1/OSC_OUT_6") (pintype "bidirectional"))
      (node (ref "Y2") (pin "1") (pinfunction "1_1") (pintype "passive"))
    )
    (net (code "33") (name "Net-(STM32-VCAP_1)") (class "Default")
      (node (ref "C19") (pin "2") (pinfunction "2_2") (pintype "passive"))
      (node (ref "STM32") (pin "31") (pinfunction "VCAP_1_31") (pintype "power_in"))
    )
    (net (code "34") (name "Net-(STM32-VCAP_2)") (class "Default")
      (node (ref "C20") (pin "2") (pinfunction "2_2") (pintype "passive"))
      (node (ref "STM32") (pin "47") (pinfunction "VCAP_2_47") (pintype "power_in"))
    )
    (net (code "35") (name "Net-(W5500-1V2O)") (class "Default")
      (node (ref "C14") (pin "1") (pinfunction "1_1") (pintype "passive"))
      (node (ref "W5500") (pin "22") (pinfunction "1V2O_22") (pintype "output"))
    )
    (net (code "36") (name "Net-(W5500-ACTLED)") (class "Default")
      (node (ref "P2") (pin "L2") (pinfunction "L2_L2") (pintype "passive"))
      (node (ref "W5500") (pin "27") (pinfunction "ACTLED_27") (pintype "output"))
    )
    (net (code "37") (name "Net-(W5500-EXRES1)") (class "Default")
      (node (ref "R19") (pin "2") (pinfunction "2_2") (pintype "passive"))
      (node (ref "W5500") (pin "10") (pinfunction "EXRES1_10") (pintype "bidirectional"))
    )
    (net (code "38") (name "Net-(W5500-LINKLED)") (class "Default")
      (node (ref "P2") (pin "L4") (pinfunction "L4_L4") (pintype "passive"))
      (node (ref "W5500") (pin "25") (pinfunction "LINKLED_25") (pintype "output"))
    )
    (net (code "39") (name "Net-(W5500-RXN)") (class "Default")
      (node (ref "C27") (pin "2") (pinfunction "2_2") (pintype "passive"))
      (node (ref "R6") (pin "1") (pinfunction "1_1") (pintype "passive"))
      (node (ref "W5500") (pin "5") (pinfunction "RXN_5") (pintype "input"))
    )
    (net (code "40") (name "Net-(W5500-RXP)") (class "Default")
      (node (ref "C26") (pin "1") (pinfunction "1_1") (pintype "passive"))
      (node (ref "R5") (pin "1") (pinfunction "1_1") (pintype "passive"))
      (node (ref "W5500") (pin "6") (pinfunction "RXP_6") (pintype "input"))
    )
    (net (code "41") (name "Net-(W5500-TOCAP)") (class "Default")
      (node (ref "C13") (pin "1") (pinfunction "1_1") (pintype "passive"))
      (node (ref "W5500") (pin "20") (pinfunction "TOCAP_20") (pintype "output"))
    )
    (net (code "42") (name "Net-(W5500-XI)") (class "Default")
      (node (ref "C15") (pin "1") (pinfunction "1_1") (pintype "passive"))
      (node (ref "R22") (pin "1") (pinfunction "1_1") (pintype "passive"))
      (node (ref "W5500") (pin "30") (pinfunction "XI_30") (pintype "input"))
      (node (ref "Y1") (pin "2") (pinfunction "2_2") (pintype "passive"))
    )
    (net (code "43") (name "Net-(W5500-XO)") (class "Default")
      (node (ref "C16") (pin "1") (pinfunction "1_1") (pintype "passive"))
      (node (ref "R22") (pin "2") (pinfunction "2_2") (pintype "passive"))
      (node (ref "W5500") (pin "31") (pinfunction "XO_31") (pintype "output"))
      (node (ref "Y1") (pin "1") (pinfunction "1_1") (pintype "passive"))
    )
    (net (code "44") (name "PLTA_ON{slash}OFF") (class "Default")
      (node (ref "PWR_ON") (pin "P$8") (pinfunction "SPARE8_P$8") (pintype "bidirectional"))
      (node (ref "SWITCH_CONNECTOR") (pin "1") (pinfunction "P_1") (pintype "passive"))
      (node (ref "U$1") (pin "50") (pinfunction "PLTA_ON/OFF_50") (pintype "bidirectional"))
      (node (ref "U$2") (pin "50") (pinfunction "PLTA_ON/OFF_50") (pintype "bidirectional"))
      (node (ref "U$3") (pin "50") (pinfunction "PLTA_ON/OFF_50") (pintype "bidirectional"))
    )
    (net (code "45") (name "PWM_1") (class "Default")
      (node (ref "Q1") (pin "3") (pinfunction "D_3") (pintype "bidirectional"))
      (node (ref "R26") (pin "2") (pinfunction "2_2") (pintype "passive"))
      (node (ref "U$1") (pin "20") (pinfunction "PWM_1_20") (pintype "bidirectional"))
      (node (ref "U$2") (pin "20") (pinfunction "PWM_1_20") (pintype "bidirectional"))
      (node (ref "U$3") (pin "20") (pinfunction "PWM_1_20") (pintype "bidirectional"))
      (node (ref "U$6") (pin "P$9") (pinfunction "PWM_1_P$9") (pintype "bidirectional"))
    )
    (net (code "46") (name "PWM_2") (class "Default")
      (node (ref "Q5") (pin "3") (pinfunction "D_3") (pintype "bidirectional"))
      (node (ref "R36") (pin "2") (pinfunction "2_2") (pintype "passive"))
      (node (ref "U$1") (pin "21") (pinfunction "PWM_2_21") (pintype "bidirectional"))
      (node (ref "U$2") (pin "21") (pinfunction "PWM_2_21") (pintype "bidirectional"))
      (node (ref "U$3") (pin "21") (pinfunction "PWM_2_21") (pintype "bidirectional"))
      (node (ref "U$6") (pin "P$8") (pinfunction "PWM_2_P$8") (pintype "bidirectional"))
    )
    (net (code "47") (name "PWM_3") (class "Default")
      (node (ref "Q2") (pin "3") (pinfunction "D_3") (pintype "bidirectional"))
      (node (ref "R29") (pin "2") (pinfunction "2_2") (pintype "passive"))
      (node (ref "U$1") (pin "22") (pinfunction "PWM_3_22") (pintype "bidirectional"))
      (node (ref "U$2") (pin "22") (pinfunction "PWM_3_22") (pintype "bidirectional"))
      (node (ref "U$3") (pin "22") (pinfunction "PWM_3_22") (pintype "bidirectional"))
      (node (ref "U$6") (pin "P$7") (pinfunction "PWM_3_P$7") (pintype "bidirectional"))
    )
    (net (code "48") (name "PWM_3V3_1") (class "Default")
      (node (ref "Q1") (pin "2") (pinfunction "S_2") (pintype "bidirectional"))
      (node (ref "R25") (pin "2") (pinfunction "2_2") (pintype "passive"))
      (node (ref "STM32") (pin "61") (pinfunction "PB8_61") (pintype "bidirectional"))
    )
    (net (code "49") (name "PWM_3V3_2") (class "Default")
      (node (ref "Q5") (pin "2") (pinfunction "S_2") (pintype "bidirectional"))
      (node (ref "R35") (pin "2") (pinfunction "2_2") (pintype "passive"))
      (node (ref "STM32") (pin "62") (pinfunction "PB9_62") (pintype "bidirectional"))
    )
    (net (code "50") (name "PWM_3V3_3") (class "Default")
      (node (ref "Q2") (pin "2") (pinfunction "S_2") (pintype "bidirectional"))
      (node (ref "R28") (pin "2") (pinfunction "2_2") (pintype "passive"))
      (node (ref "STM32") (pin "35") (pinfunction "PB14_35") (pintype "bidirectional"))
    )
    (net (code "51") (name "PWM_3V3_4") (class "Default")
      (node (ref "Q6") (pin "2") (pinfunction "S_2") (pintype "bidirectional"))
      (node (ref "R37") (pin "2") (pinfunction "2_2") (pintype "passive"))
      (node (ref "STM32") (pin "36") (pinfunction "PB15_36") (pintype "bidirectional"))
    )
    (net (code "52") (name "PWM_3V3_5") (class "Default")
      (node (ref "Q3") (pin "2") (pinfunction "S_2") (pintype "bidirectional"))
      (node (ref "R31") (pin "2") (pinfunction "2_2") (pintype "passive"))
      (node (ref "STM32") (pin "14") (pinfunction "PA0/WKUP_14") (pintype "bidirectional"))
    )
    (net (code "53") (name "PWM_3V3_6") (class "Default")
      (node (ref "Q7") (pin "2") (pinfunction "S_2") (pintype "bidirectional"))
      (node (ref "R39") (pin "2") (pinfunction "2_2") (pintype "passive"))
      (node (ref "STM32") (pin "15") (pinfunction "PA1/USART2_RTS_15") (pintype "bidirectional"))
    )
    (net (code "54") (name "PWM_3V3_7") (class "Default")
      (node (ref "Q4") (pin "2") (pinfunction "S_2") (pintype "bidirectional"))
      (node (ref "R33") (pin "2") (pinfunction "2_2") (pintype "passive"))
      (node (ref "STM32") (pin "16") (pinfunction "PA2/USART2_TX_16") (pintype "bidirectional"))
    )
    (net (code "55") (name "PWM_3V3_8") (class "Default")
      (node (ref "Q8") (pin "2") (pinfunction "S_2") (pintype "bidirectional"))
      (node (ref "R41") (pin "2") (pinfunction "2_2") (pintype "passive"))
      (node (ref "STM32") (pin "17") (pinfunction "PA3/USART2_RX_17") (pintype "bidirectional"))
    )
    (net (code "56") (name "PWM_4") (class "Default")
      (node (ref "Q6") (pin "3") (pinfunction "D_3") (pintype "bidirectional"))
      (node (ref "R38") (pin "2") (pinfunction "2_2") (pintype "passive"))
      (node (ref "U$1") (pin "23") (pinfunction "PWM_4_23") (pintype "bidirectional"))
      (node (ref "U$2") (pin "23") (pinfunction "PWM_4_23") (pintype "bidirectional"))
      (node (ref "U$3") (pin "23") (pinfunction "PWM_4_23") (pintype "bidirectional"))
      (node (ref "U$6") (pin "P$6") (pinfunction "PWM_4_P$6") (pintype "bidirectional"))
    )
    (net (code "57") (name "PWM_5") (class "Default")
      (node (ref "Q3") (pin "3") (pinfunction "D_3") (pintype "bidirectional"))
      (node (ref "R32") (pin "2") (pinfunction "2_2") (pintype "passive"))
      (node (ref "U$1") (pin "24") (pinfunction "PWM_5_24") (pintype "bidirectional"))
      (node (ref "U$2") (pin "24") (pinfunction "PWM_5_24") (pintype "bidirectional"))
      (node (ref "U$3") (pin "24") (pinfunction "PWM_5_24") (pintype "bidirectional"))
      (node (ref "U$6") (pin "P$5") (pinfunction "PWM_5_P$5") (pintype "bidirectional"))
    )
    (net (code "58") (name "PWM_6") (class "Default")
      (node (ref "Q7") (pin "3") (pinfunction "D_3") (pintype "bidirectional"))
      (node (ref "R40") (pin "2") (pinfunction "2_2") (pintype "passive"))
      (node (ref "U$1") (pin "25") (pinfunction "PWM_6_25") (pintype "bidirectional"))
      (node (ref "U$2") (pin "25") (pinfunction "PWM_6_25") (pintype "bidirectional"))
      (node (ref "U$3") (pin "25") (pinfunction "PWM_6_25") (pintype "bidirectional"))
      (node (ref "U$6") (pin "P$4") (pinfunction "PWM_6_P$4") (pintype "bidirectional"))
    )
    (net (code "59") (name "PWM_7") (class "Default")
      (node (ref "Q4") (pin "3") (pinfunction "D_3") (pintype "bidirectional"))
      (node (ref "R34") (pin "2") (pinfunction "2_2") (pintype "passive"))
      (node (ref "U$1") (pin "26") (pinfunction "PWM_7_26") (pintype "bidirectional"))
      (node (ref "U$2") (pin "26") (pinfunction "PWM_7_26") (pintype "bidirectional"))
      (node (ref "U$3") (pin "26") (pinfunction "PWM_7_26") (pintype "bidirectional"))
      (node (ref "U$6") (pin "P$3") (pinfunction "PWM_7_P$3") (pintype "bidirectional"))
    )
    (net (code "60") (name "PWM_8") (class "Default")
      (node (ref "Q8") (pin "3") (pinfunction "D_3") (pintype "bidirectional"))
      (node (ref "R42") (pin "2") (pinfunction "2_2") (pintype "passive"))
      (node (ref "U$1") (pin "27") (pinfunction "PWM_8_27") (pintype "bidirectional"))
      (node (ref "U$2") (pin "27") (pinfunction "PWM_8_27") (pintype "bidirectional"))
      (node (ref "U$3") (pin "27") (pinfunction "PWM_8_27") (pintype "bidirectional"))
      (node (ref "U$6") (pin "P$2") (pinfunction "PWM_8_P$2") (pintype "bidirectional"))
    )
    (net (code "61") (name "RESET") (class "Default")
      (node (ref "C23") (pin "2") (pinfunction "2_2") (pintype "passive"))
      (node (ref "C24") (pin "2") (pinfunction "2_2") (pintype "passive"))
      (node (ref "R27") (pin "1") (pinfunction "1_1") (pintype "passive"))
      (node (ref "RESET") (pin "3") (pinfunction "2_3") (pintype "passive"))
      (node (ref "STM32") (pin "7") (pinfunction "NRST_7") (pintype "bidirectional"))
      (node (ref "SWDIO/SWDCLK/RESET") (pin "15") (pinfunction "15_15") (pintype "passive"))
    )
    (net (code "62") (name "ROBOT_SCL") (class "Default")
      (node (ref "3.3V_ROBO_I2C") (pin "4") (pinfunction "P_4") (pintype "passive"))
      (node (ref "R18") (pin "2") (pinfunction "2_2") (pintype "passive"))
      (node (ref "STM32") (pin "29") (pinfunction "PB10_29") (pintype "bidirectional"))
      (node (ref "U$1") (pin "29") (pinfunction "ROBOT_SCL_29") (pintype "bidirectional"))
      (node (ref "U$2") (pin "29") (pinfunction "ROBOT_SCL_29") (pintype "bidirectional"))
      (node (ref "U$3") (pin "29") (pinfunction "ROBOT_SCL_29") (pintype "bidirectional"))
      (node (ref "U$8") (pin "P$6") (pinfunction "ROBOT_SCL_P$6") (pintype "bidirectional"))
    )
    (net (code "63") (name "ROBOT_SDA") (class "Default")
      (node (ref "3.3V_ROBO_I2C") (pin "2") (pinfunction "P_2") (pintype "passive"))
      (node (ref "R17") (pin "2") (pinfunction "2_2") (pintype "passive"))
      (node (ref "STM32") (pin "30") (pinfunction "PB11_30") (pintype "bidirectional"))
      (node (ref "U$1") (pin "30") (pinfunction "ROBOT_SDA_30") (pintype "bidirectional"))
      (node (ref "U$2") (pin "30") (pinfunction "ROBOT_SDA_30") (pintype "bidirectional"))
      (node (ref "U$3") (pin "30") (pinfunction "ROBOT_SDA_30") (pintype "bidirectional"))
      (node (ref "U$8") (pin "P$5") (pinfunction "ROBOT_SDA_P$5") (pintype "bidirectional"))
    )
    (net (code "64") (name "SPARE2") (class "Default")
      (node (ref "U$1") (pin "28") (pinfunction "SPARE2_28") (pintype "bidirectional"))
      (node (ref "U$2") (pin "28") (pinfunction "SPARE2_28") (pintype "bidirectional"))
      (node (ref "U$3") (pin "28") (pinfunction "SPARE2_28") (pintype "bidirectional"))
      (node (ref "U$6") (pin "P$1") (pinfunction "SPARE2_P$1") (pintype "bidirectional"))
    )
    (net (code "65") (name "SPARE3") (class "Default")
      (node (ref "U$1") (pin "33") (pinfunction "SPARE3_33") (pintype "bidirectional"))
      (node (ref "U$2") (pin "33") (pinfunction "SPARE3_33") (pintype "bidirectional"))
      (node (ref "U$3") (pin "33") (pinfunction "SPARE3_33") (pintype "bidirectional"))
      (node (ref "U$8") (pin "P$2") (pinfunction "SPARE3_P$2") (pintype "bidirectional"))
    )
    (net (code "66") (name "SPARE4") (class "Default")
      (node (ref "U$1") (pin "34") (pinfunction "SPARE4_34") (pintype "bidirectional"))
      (node (ref "U$2") (pin "34") (pinfunction "SPARE4_34") (pintype "bidirectional"))
      (node (ref "U$3") (pin "34") (pinfunction "SPARE4_34") (pintype "bidirectional"))
      (node (ref "U$8") (pin "P$1") (pinfunction "SPARE4_P$1") (pintype "bidirectional"))
    )
    (net (code "67") (name "SPARE5") (class "Default")
      (node (ref "SWITCH_CONN") (pin "P$9") (pinfunction "SPARE5_P$9") (pintype "bidirectional"))
      (node (ref "U$1") (pin "35") (pinfunction "SPARE5_35") (pintype "bidirectional"))
      (node (ref "U$2") (pin "35") (pinfunction "SPARE5_35") (pintype "bidirectional"))
      (node (ref "U$3") (pin "35") (pinfunction "SPARE5_35") (pintype "bidirectional"))
    )
    (net (code "68") (name "SPARE6") (class "Default")
      (node (ref "SWITCH_CONN") (pin "P$8") (pinfunction "SPARE6_P$8") (pintype "bidirectional"))
      (node (ref "U$1") (pin "36") (pinfunction "SPARE6_36") (pintype "bidirectional"))
      (node (ref "U$2") (pin "36") (pinfunction "SPARE6_36") (pintype "bidirectional"))
      (node (ref "U$3") (pin "36") (pinfunction "SPARE6_36") (pintype "bidirectional"))
    )
    (net (code "69") (name "SPARE7") (class "Default")
      (node (ref "SWITCH_CONN") (pin "P$1") (pinfunction "SPARE7_P$1") (pintype "bidirectional"))
      (node (ref "U$1") (pin "43") (pinfunction "SPARE7_43") (pintype "bidirectional"))
      (node (ref "U$2") (pin "43") (pinfunction "SPARE7_43") (pintype "bidirectional"))
      (node (ref "U$3") (pin "43") (pinfunction "SPARE7_43") (pintype "bidirectional"))
    )
    (net (code "70") (name "SPI_CLK") (class "Default")
      (node (ref "STM32") (pin "21") (pinfunction "PA5/SPI1_SCK_21") (pintype "bidirectional"))
      (node (ref "W5500") (pin "33") (pinfunction "SCLK_33") (pintype "input"))
    )
    (net (code "71") (name "SPI_MISO") (class "Default")
      (node (ref "STM32") (pin "22") (pinfunction "PA6/SPI1_MISO_22") (pintype "bidirectional"))
      (node (ref "W5500") (pin "34") (pinfunction "MISO_34") (pintype "output"))
    )
    (net (code "72") (name "SPI_MOSI") (class "Default")
      (node (ref "STM32") (pin "23") (pinfunction "PA7/SPI1_MOSI_23") (pintype "bidirectional"))
      (node (ref "W5500") (pin "35") (pinfunction "MOSI_35") (pintype "input"))
    )
    (net (code "73") (name "SPI_SS") (class "Default")
      (node (ref "STM32") (pin "20") (pinfunction "PA4/USART2_CK_20") (pintype "bidirectional"))
      (node (ref "W5500") (pin "32") (pinfunction "~{SCSN}_32") (pintype "input"))
    )
    (net (code "74") (name "SWCLK") (class "Default")
      (node (ref "STM32") (pin "49") (pinfunction "PA14/JTCK-SWCLK_49") (pintype "bidirectional"))
      (node (ref "SWDIO/SWDCLK/RESET") (pin "9") (pinfunction "9_9") (pintype "passive"))
    )
    (net (code "75") (name "SWDIO") (class "Default")
      (node (ref "STM32") (pin "46") (pinfunction "PA13/JMS-SWDIO_46") (pintype "bidirectional"))
      (node (ref "SWDIO/SWDCLK/RESET") (pin "7") (pinfunction "7_7") (pintype "passive"))
    )
    (net (code "76") (name "SWITCH_1") (class "Default")
      (node (ref "R10") (pin "2") (pinfunction "2_2") (pintype "passive"))
      (node (ref "STM32") (pin "34") (pinfunction "PB13_34") (pintype "bidirectional"))
      (node (ref "SWITCH_CONN") (pin "P$6") (pinfunction "SWITCH_1_P$6") (pintype "bidirectional"))
      (node (ref "SWITCH_CONNECTOR") (pin "3") (pinfunction "P_3") (pintype "passive"))
      (node (ref "U$1") (pin "38") (pinfunction "SWITCH_1_38") (pintype "output"))
      (node (ref "U$2") (pin "38") (pinfunction "SWITCH_1_38") (pintype "output"))
      (node (ref "U$3") (pin "38") (pinfunction "SWITCH_1_38") (pintype "output"))
    )
    (net (code "77") (name "SWITCH_2") (class "Default")
      (node (ref "R11") (pin "2") (pinfunction "2_2") (pintype "passive"))
      (node (ref "STM32") (pin "37") (pinfunction "PC6_37") (pintype "bidirectional"))
      (node (ref "SWITCH_CONN") (pin "P$5") (pinfunction "SWITCH_2_P$5") (pintype "bidirectional"))
      (node (ref "SWITCH_CONNECTOR") (pin "2") (pinfunction "P_2") (pintype "passive"))
      (node (ref "U$1") (pin "39") (pinfunction "SWITCH_2_39") (pintype "output"))
      (node (ref "U$2") (pin "39") (pinfunction "SWITCH_2_39") (pintype "output"))
      (node (ref "U$3") (pin "39") (pinfunction "SWITCH_2_39") (pintype "output"))
    )
    (net (code "78") (name "SWITCH_3") (class "Default")
      (node (ref "R12") (pin "2") (pinfunction "2_2") (pintype "passive"))
      (node (ref "STM32") (pin "38") (pinfunction "PC7_38") (pintype "bidirectional"))
      (node (ref "SWITCH_CONN") (pin "P$4") (pinfunction "SWITCH_3_P$4") (pintype "bidirectional"))
      (node (ref "SWITCH_CONNECTOR") (pin "6") (pinfunction "P_6") (pintype "passive"))
      (node (ref "U$1") (pin "40") (pinfunction "SWITCH_3_40") (pintype "output"))
      (node (ref "U$2") (pin "40") (pinfunction "SWITCH_3_40") (pintype "output"))
      (node (ref "U$3") (pin "40") (pinfunction "SWITCH_3_40") (pintype "output"))
    )
    (net (code "79") (name "SWITCH_4") (class "Default")
      (node (ref "R13") (pin "2") (pinfunction "2_2") (pintype "passive"))
      (node (ref "STM32") (pin "24") (pinfunction "PC4_24") (pintype "bidirectional"))
      (node (ref "SWITCH_CONN") (pin "P$3") (pinfunction "SWITCH_4_P$3") (pintype "bidirectional"))
      (node (ref "SWITCH_CONNECTOR") (pin "7") (pinfunction "P_7") (pintype "passive"))
      (node (ref "U$1") (pin "41") (pinfunction "SWITCH_4_41") (pintype "output"))
      (node (ref "U$2") (pin "41") (pinfunction "SWITCH_4_41") (pintype "output"))
      (node (ref "U$3") (pin "41") (pinfunction "SWITCH_4_41") (pintype "output"))
    )
    (net (code "80") (name "SWITCH_5") (class "Default")
      (node (ref "R14") (pin "2") (pinfunction "2_2") (pintype "passive"))
      (node (ref "STM32") (pin "27") (pinfunction "PB1_27") (pintype "bidirectional"))
      (node (ref "SWITCH_CONN") (pin "P$2") (pinfunction "SWITCH_5_P$2") (pintype "bidirectional"))
      (node (ref "SWITCH_CONNECTOR") (pin "8") (pinfunction "P_8") (pintype "passive"))
      (node (ref "U$1") (pin "42") (pinfunction "SWITCH_5_42") (pintype "output"))
      (node (ref "U$2") (pin "42") (pinfunction "SWITCH_5_42") (pintype "output"))
      (node (ref "U$3") (pin "42") (pinfunction "SWITCH_5_42") (pintype "output"))
    )
    (net (code "81") (name "VBAT") (class "Default")
      (node (ref "STM32") (pin "1") (pinfunction "VBAT_1") (pintype "power_in"))
    )
    (net (code "82") (name "VBUS") (class "Default")
      (node (ref "D5") (pin "A") (pinfunction "A_A") (pintype "passive"))
      (node (ref "PROGRAMMING") (pin "VBUS") (pinfunction "VBUS_VBUS") (pintype "power_in"))
    )
    (net (code "83") (name "VBUS_3.3") (class "Default")
      (node (ref "R20") (pin "2") (pinfunction "2_2") (pintype "passive"))
      (node (ref "R21") (pin "1") (pinfunction "1_1") (pintype "passive"))
      (node (ref "STM32") (pin "42") (pinfunction "PA9_42") (pintype "bidirectional"))
    )
    (net (code "84") (name "unconnected-(P2-PadR4)") (class "Default")
      (node (ref "P2") (pin "R4") (pinfunction "R4_R4") (pintype "input"))
    )
    (net (code "85") (name "unconnected-(P2-PadR5)") (class "Default")
      (node (ref "P2") (pin "R5") (pinfunction "R5_R5") (pintype "input"))
    )
    (net (code "86") (name "unconnected-(P2-PadR6)") (class "Default")
      (node (ref "P2") (pin "R6") (pinfunction "R6_R6") (pintype "input"))
    )
    (net (code "87") (name "unconnected-(PROGRAMMING-PadID)") (class "Default")
      (node (ref "PROGRAMMING") (pin "ID") (pinfunction "ID_ID") (pintype "bidirectional"))
    )
    (net (code "88") (name "unconnected-(STM32-PA10-Pad43)") (class "Default")
      (node (ref "STM32") (pin "43") (pinfunction "PA10_43") (pintype "bidirectional"))
    )
    (net (code "89") (name "unconnected-(STM32-PA15-Pad50)") (class "Default")
      (node (ref "STM32") (pin "50") (pinfunction "PA15_50") (pintype "bidirectional"))
    )
    (net (code "90") (name "unconnected-(STM32-PB2{slash}BOOT1-Pad28)") (class "Default")
      (node (ref "STM32") (pin "28") (pinfunction "PB2/BOOT1_28") (pintype "bidirectional"))
    )
    (net (code "91") (name "unconnected-(STM32-PB3-Pad55)") (class "Default")
      (node (ref "STM32") (pin "55") (pinfunction "PB3_55") (pintype "bidirectional"))
    )
    (net (code "92") (name "unconnected-(STM32-PB4-Pad56)") (class "Default")
      (node (ref "STM32") (pin "56") (pinfunction "PB4_56") (pintype "bidirectional"))
    )
    (net (code "93") (name "unconnected-(STM32-PB5-Pad57)") (class "Default")
      (node (ref "STM32") (pin "57") (pinfunction "PB5_57") (pintype "bidirectional"))
    )
    (net (code "94") (name "unconnected-(STM32-PC8-Pad39)") (class "Default")
      (node (ref "STM32") (pin "39") (pinfunction "PC8_39") (pintype "bidirectional"))
    )
    (net (code "95") (name "unconnected-(STM32-PC9-Pad40)") (class "Default")
      (node (ref "STM32") (pin "40") (pinfunction "PC9_40") (pintype "bidirectional"))
    )
    (net (code "96") (name "unconnected-(STM32-PC10-Pad51)") (class "Default")
      (node (ref "STM32") (pin "51") (pinfunction "PC10_51") (pintype "bidirectional"))
    )
    (net (code "97") (name "unconnected-(STM32-PC11-Pad52)") (class "Default")
      (node (ref "STM32") (pin "52") (pinfunction "PC11_52") (pintype "bidirectional"))
    )
    (net (code "98") (name "unconnected-(STM32-PC12-Pad53)") (class "Default")
      (node (ref "STM32") (pin "53") (pinfunction "PC12_53") (pintype "bidirectional"))
    )
    (net (code "99") (name "unconnected-(STM32-PD2-Pad54)") (class "Default")
      (node (ref "STM32") (pin "54") (pinfunction "PD2_54") (pintype "bidirectional"))
    )
    (net (code "100") (name "unconnected-(SWDIO/SWDCLK/RESET-Pad3)") (class "Default")
      (node (ref "SWDIO/SWDCLK/RESET") (pin "3") (pinfunction "3_3") (pintype "passive"))
    )
    (net (code "101") (name "unconnected-(SWDIO/SWDCLK/RESET-Pad5)") (class "Default")
      (node (ref "SWDIO/SWDCLK/RESET") (pin "5") (pinfunction "5_5") (pintype "passive"))
    )
    (net (code "102") (name "unconnected-(SWDIO/SWDCLK/RESET-Pad11)") (class "Default")
      (node (ref "SWDIO/SWDCLK/RESET") (pin "11") (pinfunction "11_11") (pintype "passive"))
    )
    (net (code "103") (name "unconnected-(SWDIO/SWDCLK/RESET-Pad13)") (class "Default")
      (node (ref "SWDIO/SWDCLK/RESET") (pin "13") (pinfunction "13_13") (pintype "passive"))
    )
    (net (code "104") (name "unconnected-(SWDIO/SWDCLK/RESET-Pad17)") (class "Default")
      (node (ref "SWDIO/SWDCLK/RESET") (pin "17") (pinfunction "17_17") (pintype "passive"))
    )
    (net (code "105") (name "unconnected-(SWDIO/SWDCLK/RESET-Pad19)") (class "Default")
      (node (ref "SWDIO/SWDCLK/RESET") (pin "19") (pinfunction "19_19") (pintype "passive"))
    )
    (net (code "106") (name "unconnected-(W5500-DNC-Pad7)") (class "Default")
      (node (ref "W5500") (pin "7") (pinfunction "DNC_7") (pintype "bidirectional"))
    )
    (net (code "107") (name "unconnected-(W5500-DUPLED-Pad26)") (class "Default")
      (node (ref "W5500") (pin "26") (pinfunction "DUPLED_26") (pintype "output"))
    )
    (net (code "108") (name "unconnected-(W5500-PMODE0-Pad45)") (class "Default")
      (node (ref "W5500") (pin "45") (pinfunction "PMODE0_45") (pintype "input"))
    )
    (net (code "109") (name "unconnected-(W5500-PMODE1-Pad44)") (class "Default")
      (node (ref "W5500") (pin "44") (pinfunction "PMODE1_44") (pintype "input"))
    )
    (net (code "110") (name "unconnected-(W5500-PMODE2-Pad43)") (class "Default")
      (node (ref "W5500") (pin "43") (pinfunction "PMODE2_43") (pintype "input"))
    )
    (net (code "111") (name "unconnected-(W5500-RSVD2-Pad38)") (class "Default")
      (node (ref "W5500") (pin "38") (pinfunction "RSVD2_38") (pintype "input"))
    )
    (net (code "112") (name "unconnected-(W5500-RSVD3-Pad39)") (class "Default")
      (node (ref "W5500") (pin "39") (pinfunction "RSVD3_39") (pintype "input"))
    )
    (net (code "113") (name "unconnected-(W5500-RSVD4-Pad40)") (class "Default")
      (node (ref "W5500") (pin "40") (pinfunction "RSVD4_40") (pintype "input"))
    )
    (net (code "114") (name "unconnected-(W5500-RSVD5-Pad41)") (class "Default")
      (node (ref "W5500") (pin "41") (pinfunction "RSVD5_41") (pintype "input"))
    )
    (net (code "115") (name "unconnected-(W5500-RSVD6-Pad42)") (class "Default")
      (node (ref "W5500") (pin "42") (pinfunction "RSVD6_42") (pintype "input"))
    )
    (net (code "116") (name "unconnected-(W5500-SPDLED-Pad24)") (class "Default")
      (node (ref "W5500") (pin "24") (pinfunction "SPDLED_24") (pintype "output"))
    )
    (net (code "117") (name "unconnected-(W5500-VBG-Pad18)") (class "Default")
      (node (ref "W5500") (pin "18") (pinfunction "VBG_18") (pintype "output"))
    )
  )
)
